# A6SS-3.net
KiCad netlist of a schematic drawn in EAGLE
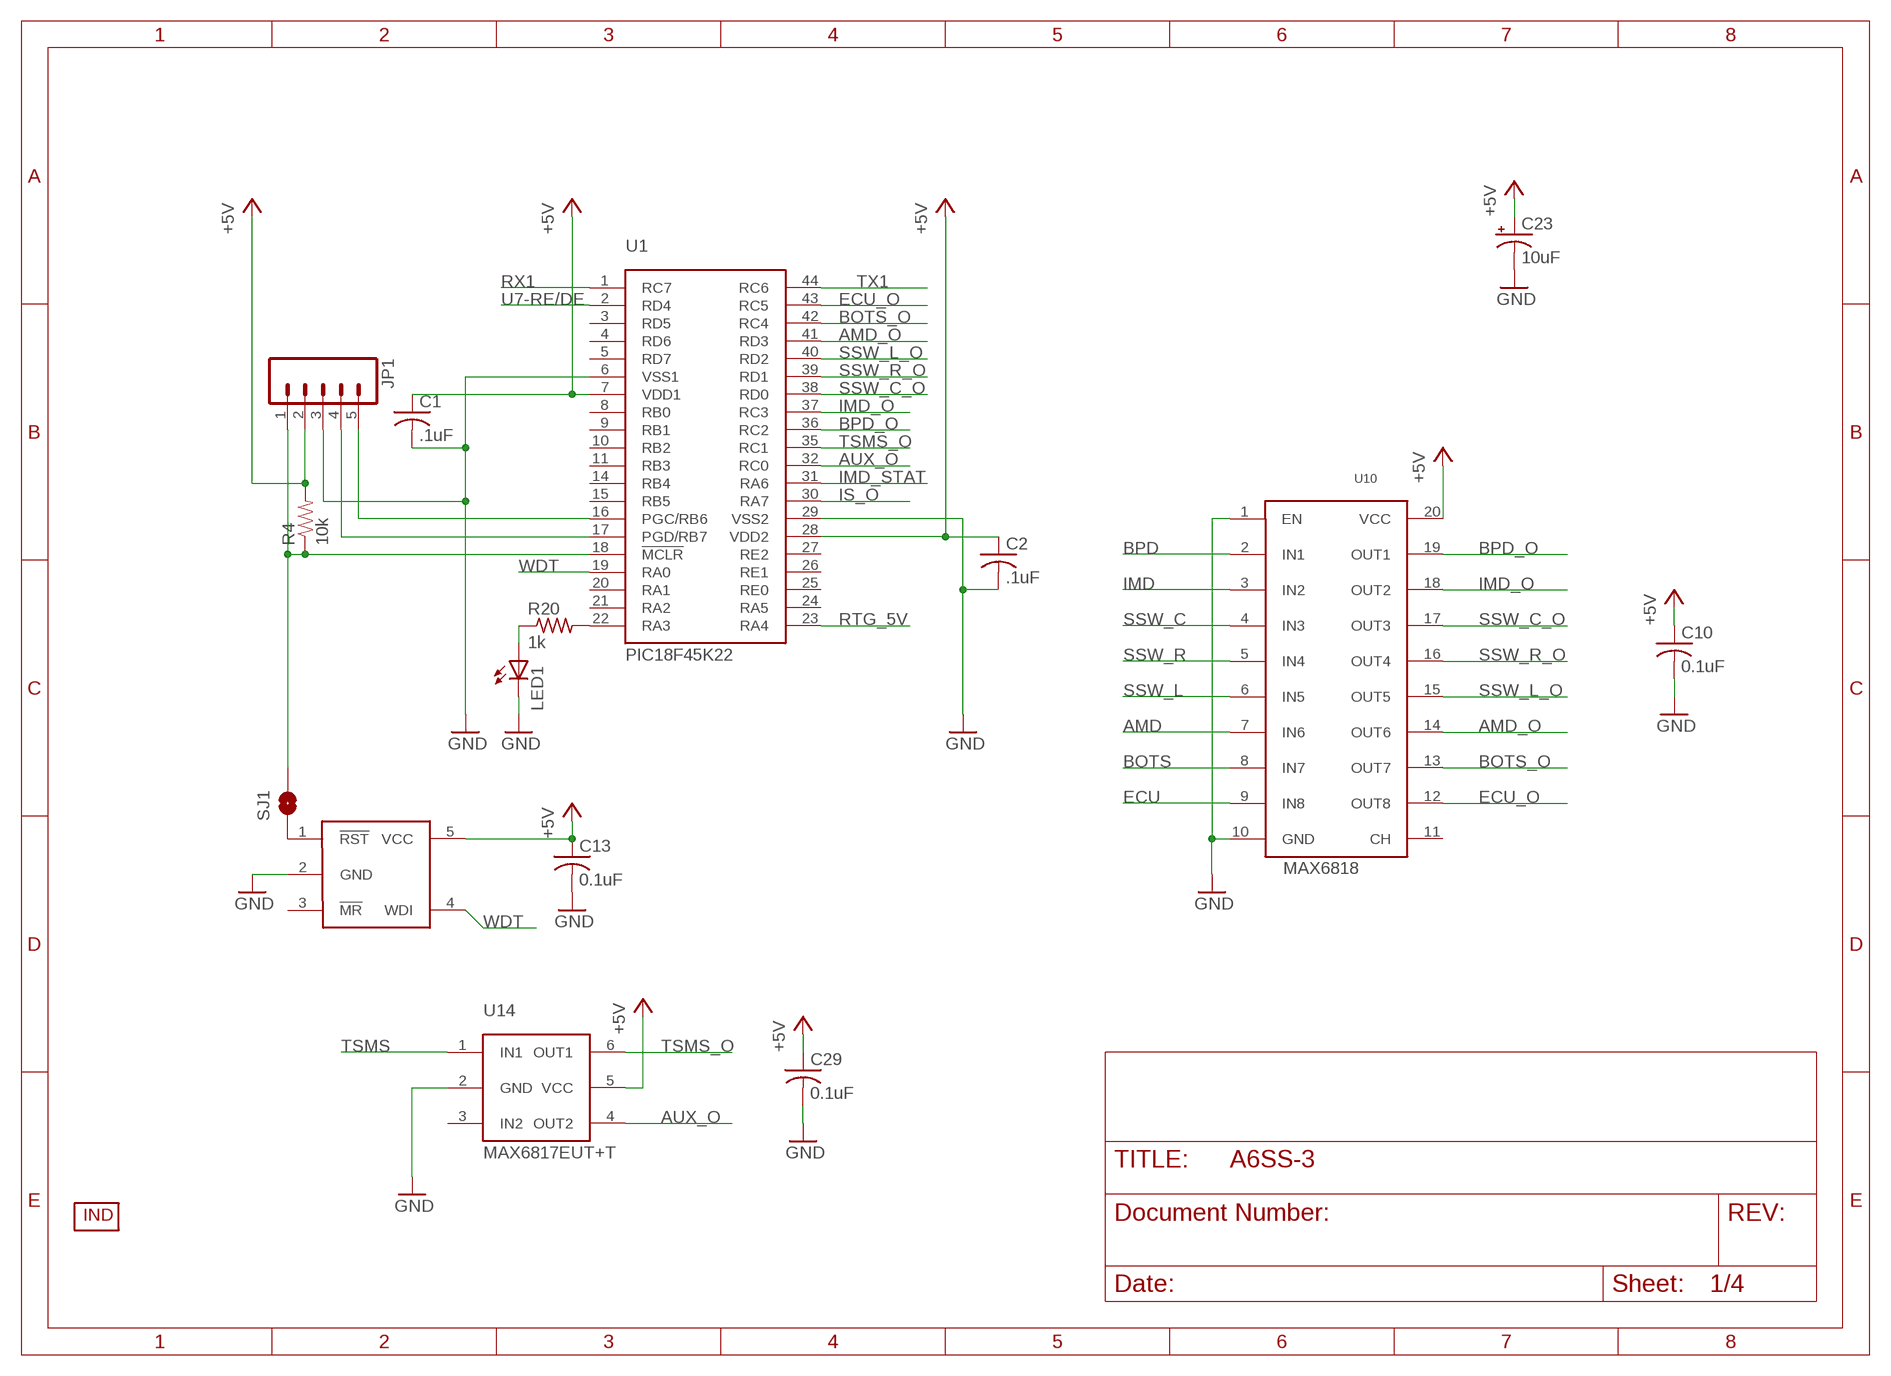
[diagram p0: schematic, sheet 1]
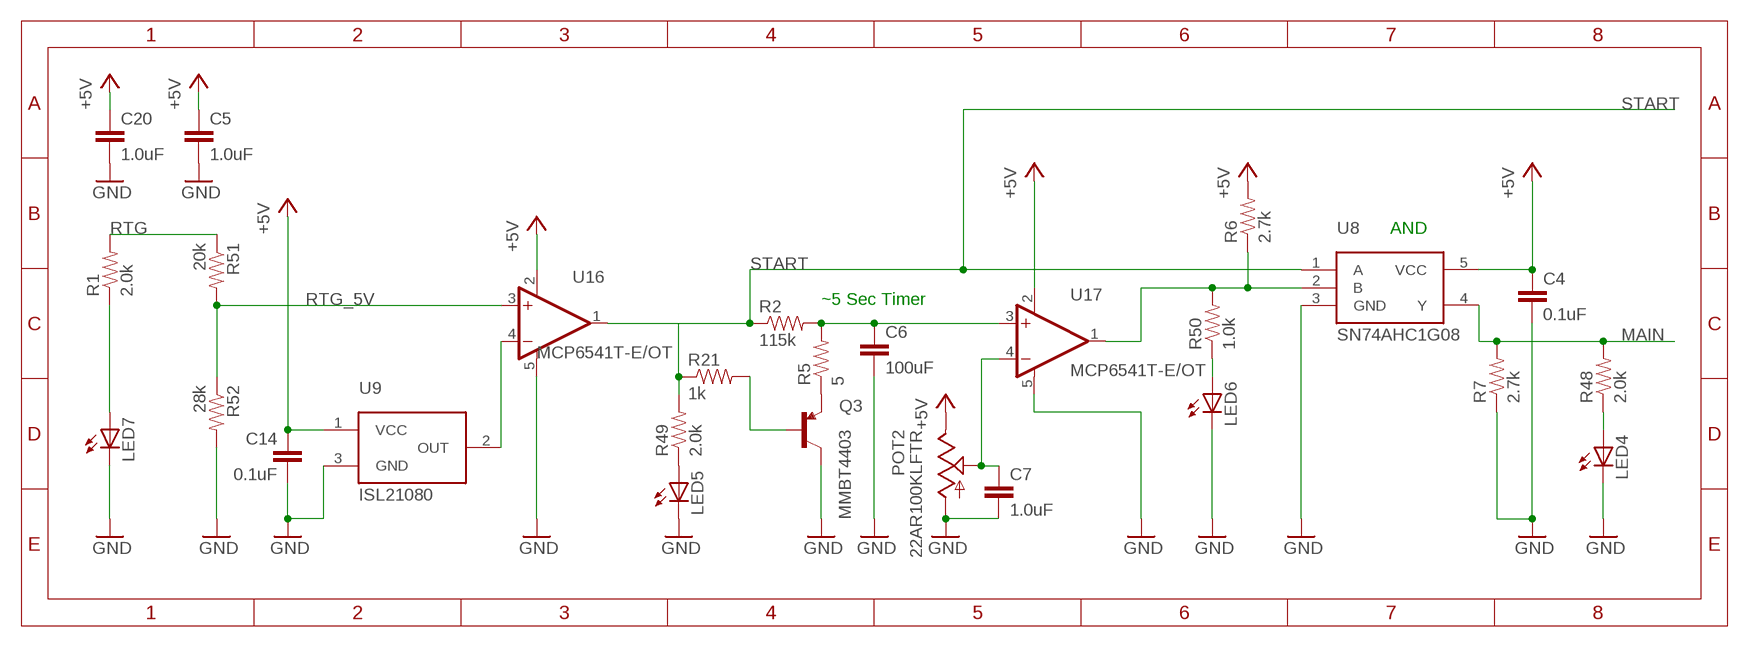
[diagram p1: schematic, sheet 2]
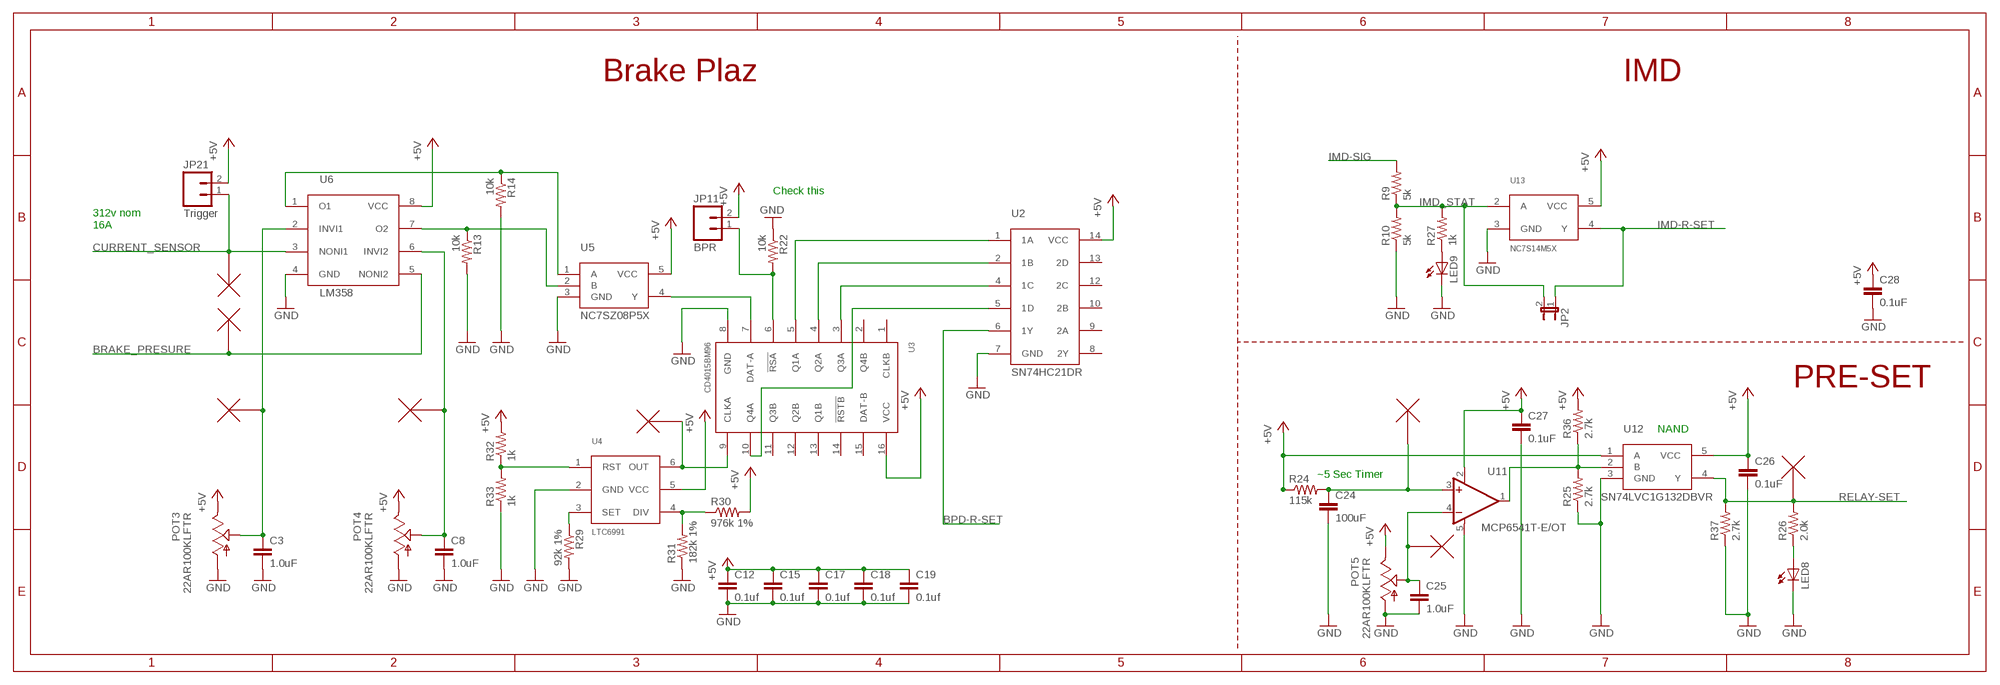
[diagram p2: schematic, sheet 3]
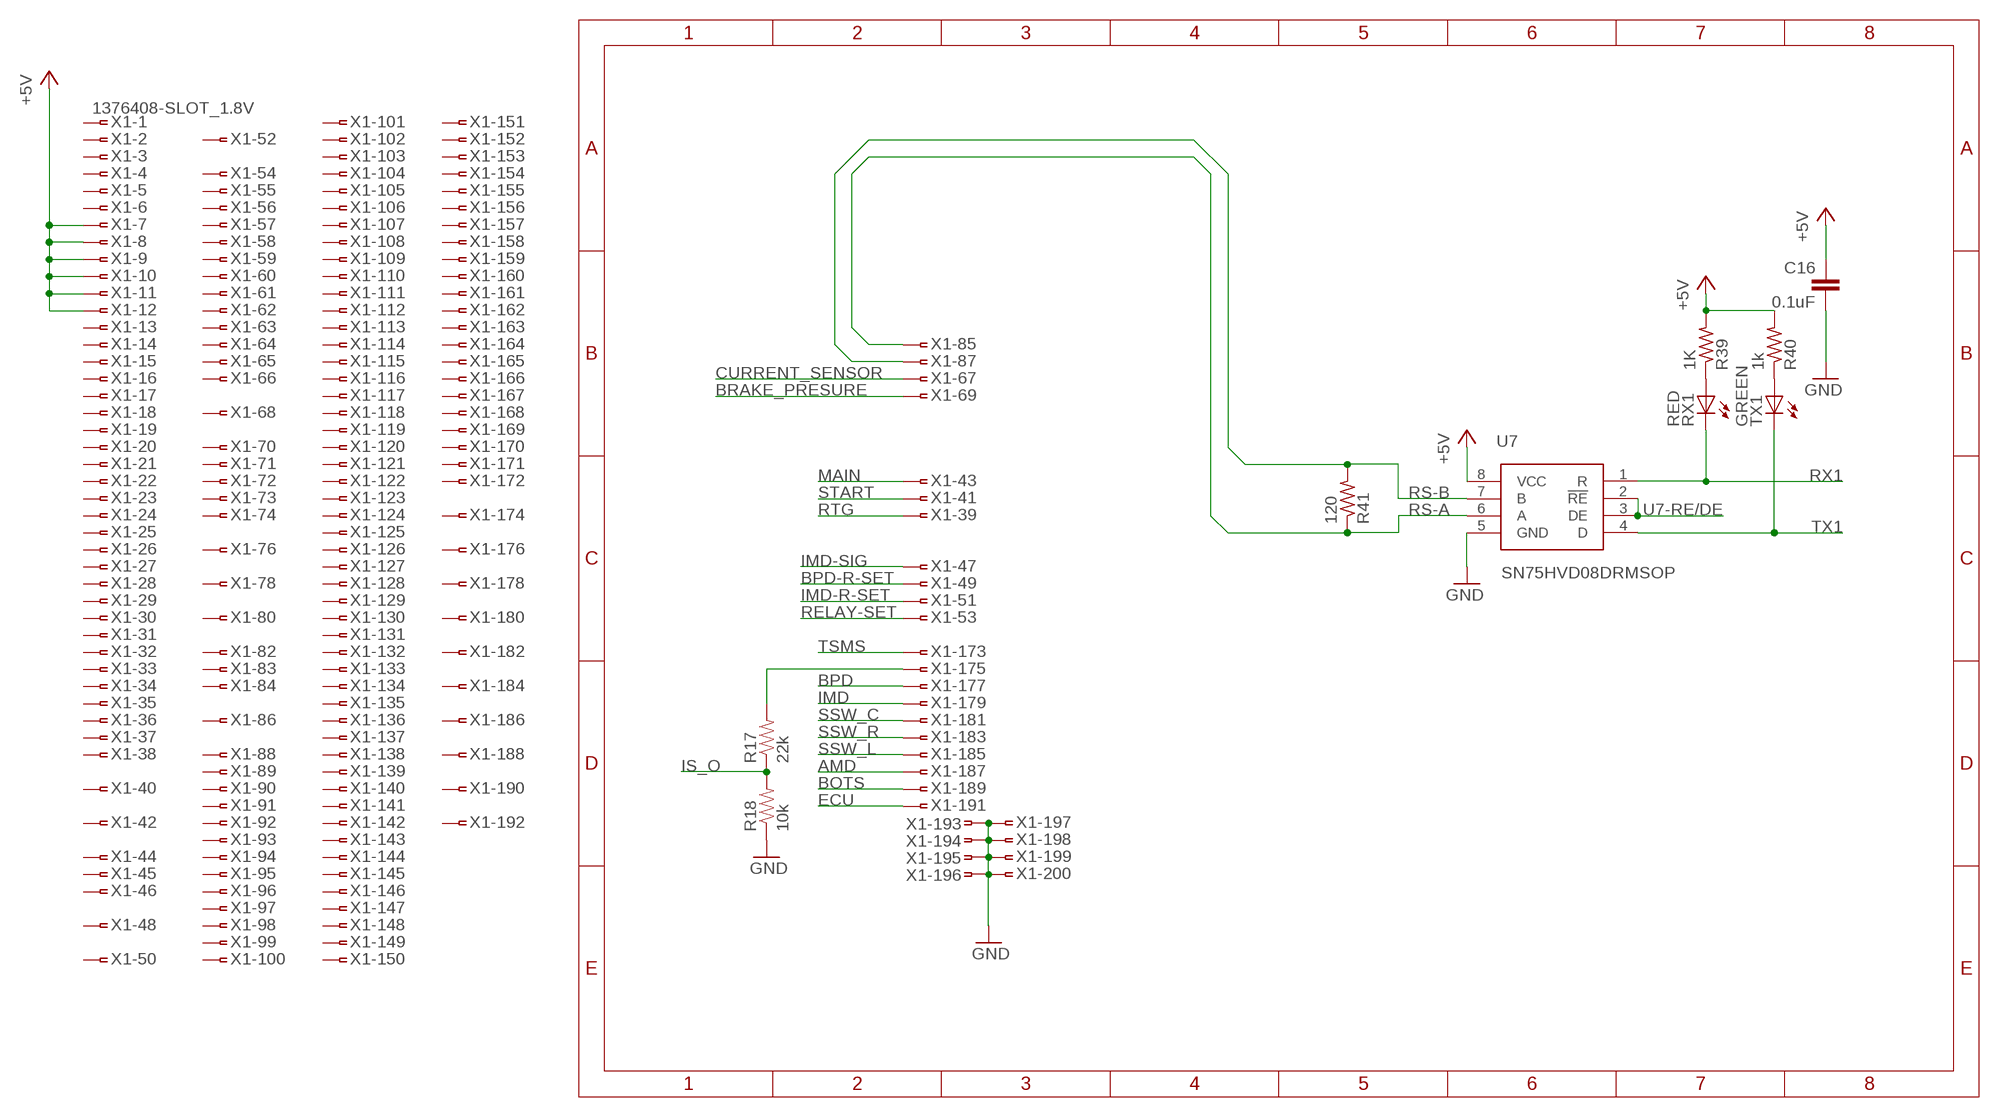
[diagram p3: schematic, sheet 4]

(export (version "E")
  (design (tool "Eeschema 10.0.6"))
  (components
    (comp (ref "C1")
      (value ".1uF")
      (footprint "eagle-import:C0603")
      (libsource (lib "eagle-import") (part "C-USC0603"))
    )
    (comp (ref "C2")
      (value ".1uF")
      (footprint "eagle-import:C0603")
      (libsource (lib "eagle-import") (part "C-USC0603"))
    )
    (comp (ref "C10")
      (value "0.1uF")
      (footprint "eagle-import:C0603")
      (libsource (lib "eagle-import") (part "C-USC0603"))
    )
    (comp (ref "C13")
      (value "0.1uF")
      (footprint "eagle-import:C0603")
      (libsource (lib "eagle-import") (part "C-USC0603"))
    )
    (comp (ref "C23")
      (value "10uF")
      (footprint "eagle-import:EIA3216")
      (libsource (lib "eagle-import") (part "10UF-TANT"))
    )
    (comp (ref "C29")
      (value "0.1uF")
      (footprint "eagle-import:C0603")
      (libsource (lib "eagle-import") (part "C-USC0603"))
    )
    (comp (ref "JP1")
      (value "M05LOCK_LONGPADS")
      (footprint "eagle-import:1X05_LOCK_LONGPADS")
      (libsource (lib "eagle-import") (part "M05LOCK_LONGPADS"))
    )
    (comp (ref "LED1")
      (value "LEDCHIPLED_0603")
      (footprint "eagle-import:CHIPLED_0603")
      (libsource (lib "eagle-import") (part "LEDCHIPLED_0603"))
    )
    (comp (ref "R4")
      (value "10k")
      (footprint "eagle-import:0603-RES")
      (libsource (lib "eagle-import") (part "RESISTOR0603-RES"))
    )
    (comp (ref "R20")
      (value "1k")
      (footprint "eagle-import:R0603")
      (libsource (lib "eagle-import") (part "R-US_R0603"))
    )
    (comp (ref "SJ1")
      (value "SOLDERJUMPERNO")
      (footprint "eagle-import:SJ_2S-NO")
      (libsource (lib "eagle-import") (part "SOLDERJUMPERNO"))
    )
    (comp (ref "U$1")
      (value "INDPK1")
      (footprint "eagle-import:PICKIT-PIN-1")
      (libsource (lib "eagle-import") (part "INDPK1"))
    )
    (comp (ref "U1")
      (value "PIC18F45K22")
      (footprint "eagle-import:TQFP-44")
      (libsource (lib "eagle-import") (part "PIC18F45K22"))
    )
    (comp (ref "U10")
      (value "MAX6818")
      (footprint "eagle-import:SSOP-20")
      (libsource (lib "eagle-import") (part "MAX6818"))
    )
    (comp (ref "U14")
      (value "MAX6817EUT+T")
      (footprint "eagle-import:SOT23-6")
      (libsource (lib "eagle-import") (part "MAX6817EUT+T"))
    )
    (comp (ref "U15")
      (value "MAX823")
      (footprint "eagle-import:SOT23-5L")
      (libsource (lib "eagle-import") (part "MAX823"))
    )
    (comp (ref "BPR")
      (value "TESTPOINT")
      (footprint "eagle-import:R0603")
      (libsource (lib "eagle-import") (part "TESTPOINT"))
    )
    (comp (ref "C3")
      (value "1.0uF")
      (footprint "eagle-import:0805")
      (libsource (lib "eagle-import") (part "1.0UF-25V-+80/-20(0805)"))
    )
    (comp (ref "C8")
      (value "1.0uF")
      (footprint "eagle-import:0805")
      (libsource (lib "eagle-import") (part "1.0UF-25V-+80/-20(0805)"))
    )
    (comp (ref "C12")
      (value "0.1uf")
      (footprint "eagle-import:0603-CAP")
      (libsource (lib "eagle-import") (part "SparkFun-Passives_CAP0603-CAP"))
    )
    (comp (ref "C15")
      (value "0.1uf")
      (footprint "eagle-import:0603-CAP")
      (libsource (lib "eagle-import") (part "SparkFun-Passives_CAP0603-CAP"))
    )
    (comp (ref "C17")
      (value "0.1uf")
      (footprint "eagle-import:0603-CAP")
      (libsource (lib "eagle-import") (part "SparkFun-Passives_CAP0603-CAP"))
    )
    (comp (ref "C18")
      (value "0.1uf")
      (footprint "eagle-import:0603-CAP")
      (libsource (lib "eagle-import") (part "SparkFun-Passives_CAP0603-CAP"))
    )
    (comp (ref "C19")
      (value "0.1uf")
      (footprint "eagle-import:0805")
      (libsource (lib "eagle-import") (part "SparkFun-Passives_CAP0805"))
    )
    (comp (ref "C24")
      (value "100uF")
      (footprint "eagle-import:1206")
      (libsource (lib "eagle-import") (part "CAP1206"))
    )
    (comp (ref "C25")
      (value "1.0uF")
      (footprint "eagle-import:0805")
      (libsource (lib "eagle-import") (part "SparkFun-Passives_CAP0805"))
    )
    (comp (ref "C26")
      (value "0.1uF")
      (footprint "eagle-import:0603-CAP")
      (libsource (lib "eagle-import") (part "SparkFun-Passives_CAP0603-CAP"))
    )
    (comp (ref "C27")
      (value "0.1uF")
      (footprint "eagle-import:0603-CAP")
      (libsource (lib "eagle-import") (part "SparkFun-Passives_CAP0603-CAP"))
    )
    (comp (ref "C28")
      (value "0.1uF")
      (footprint "eagle-import:0805")
      (libsource (lib "eagle-import") (part "SparkFun-Passives_CAP0805"))
    )
    (comp (ref "CLK")
      (value "TESTPOINT")
      (footprint "eagle-import:R0603")
      (libsource (lib "eagle-import") (part "TESTPOINT"))
    )
    (comp (ref "CS")
      (value "TESTPOINT")
      (footprint "eagle-import:R0603")
      (libsource (lib "eagle-import") (part "TESTPOINT"))
    )
    (comp (ref "CST")
      (value "TESTPOINT")
      (footprint "eagle-import:R0603")
      (libsource (lib "eagle-import") (part "TESTPOINT"))
    )
    (comp (ref "JP2")
      (value "JUMPER-2SMD-NO")
      (footprint "eagle-import:SJ_2S-NO")
      (libsource (lib "eagle-import") (part "JUMPER-2SMD-NO"))
    )
    (comp (ref "JP11")
      (value "BPR")
      (footprint "eagle-import:MOLEX-1X2_LOCK")
      (libsource (lib "eagle-import") (part "M02POLAR_LOCK"))
    )
    (comp (ref "JP21")
      (value "Trigger")
      (footprint "eagle-import:MOLEX-1X2_LOCK")
      (libsource (lib "eagle-import") (part "M02POLAR_LOCK"))
    )
    (comp (ref "LED8")
      (value "LEDCHIPLED_0603")
      (footprint "eagle-import:CHIPLED_0603")
      (libsource (lib "eagle-import") (part "LEDCHIPLED_0603"))
    )
    (comp (ref "LED9")
      (value "LEDCHIPLED_0603")
      (footprint "eagle-import:CHIPLED_0603")
      (libsource (lib "eagle-import") (part "LEDCHIPLED_0603"))
    )
    (comp (ref "PCG")
      (value "TESTPOINT")
      (footprint "eagle-import:R0603")
      (libsource (lib "eagle-import") (part "TESTPOINT"))
    )
    (comp (ref "POT3")
      (value "22AR100KLFTR")
      (footprint "eagle-import:22AR100KLFTR")
      (libsource (lib "eagle-import") (part "22AR100KLFTR"))
    )
    (comp (ref "POT4")
      (value "22AR100KLFTR")
      (footprint "eagle-import:22AR100KLFTR")
      (libsource (lib "eagle-import") (part "22AR100KLFTR"))
    )
    (comp (ref "POT5")
      (value "22AR100KLFTR")
      (footprint "eagle-import:22AR100KLFTR")
      (libsource (lib "eagle-import") (part "22AR100KLFTR"))
    )
    (comp (ref "R9")
      (value "5k")
      (footprint "eagle-import:0603-RES")
      (libsource (lib "eagle-import") (part "RESISTOR0603-RES"))
    )
    (comp (ref "R10")
      (value "5k")
      (footprint "eagle-import:0603-RES")
      (libsource (lib "eagle-import") (part "RESISTOR0603-RES"))
    )
    (comp (ref "R13")
      (value "10k")
      (footprint "eagle-import:0603-RES")
      (libsource (lib "eagle-import") (part "SparkFun-Resistors_RESISTOR0603-RES"))
    )
    (comp (ref "R14")
      (value "10k")
      (footprint "eagle-import:0603-RES")
      (libsource (lib "eagle-import") (part "SparkFun-Resistors_RESISTOR0603-RES"))
    )
    (comp (ref "R22")
      (value "10k")
      (footprint "eagle-import:0603-RES")
      (libsource (lib "eagle-import") (part "SparkFun-Resistors_RESISTOR0603-RES"))
    )
    (comp (ref "R24")
      (value "115k")
      (footprint "eagle-import:1206")
      (libsource (lib "eagle-import") (part "SparkFun-Resistors_RESISTOR1206"))
    )
    (comp (ref "R25")
      (value "2.7k")
      (footprint "eagle-import:0603-RES")
      (libsource (lib "eagle-import") (part "RESISTOR0603-RES"))
    )
    (comp (ref "R26")
      (value "2.0k")
      (footprint "eagle-import:0603-RES")
      (libsource (lib "eagle-import") (part "RESISTOR0603-RES"))
    )
    (comp (ref "R27")
      (value "1k")
      (footprint "eagle-import:0603-RES")
      (libsource (lib "eagle-import") (part "RESISTOR0603-RES"))
    )
    (comp (ref "R29")
      (value "92k 1%")
      (footprint "eagle-import:0603-RES")
      (libsource (lib "eagle-import") (part "SparkFun-Resistors_RESISTOR0603-RES"))
    )
    (comp (ref "R30")
      (value "976k 1%")
      (footprint "eagle-import:0603-RES")
      (libsource (lib "eagle-import") (part "SparkFun-Resistors_RESISTOR0603-RES"))
    )
    (comp (ref "R31")
      (value "182k 1%")
      (footprint "eagle-import:0603-RES")
      (libsource (lib "eagle-import") (part "SparkFun-Resistors_RESISTOR0603-RES"))
    )
    (comp (ref "R32")
      (value "1k")
      (footprint "eagle-import:0603-RES")
      (libsource (lib "eagle-import") (part "SparkFun-Resistors_RESISTOR0603-RES"))
    )
    (comp (ref "R33")
      (value "1k")
      (footprint "eagle-import:0603-RES")
      (libsource (lib "eagle-import") (part "SparkFun-Resistors_RESISTOR0603-RES"))
    )
    (comp (ref "R36")
      (value "2.7k")
      (footprint "eagle-import:0603-RES")
      (libsource (lib "eagle-import") (part "RESISTOR0603-RES"))
    )
    (comp (ref "R37")
      (value "2.7k")
      (footprint "eagle-import:0603-RES")
      (libsource (lib "eagle-import") (part "RESISTOR0603-RES"))
    )
    (comp (ref "RST")
      (value "TESTPOINT")
      (footprint "eagle-import:R0603")
      (libsource (lib "eagle-import") (part "TESTPOINT"))
    )
    (comp (ref "U$2")
      (value "TESTPOINT")
      (footprint "eagle-import:R0603")
      (libsource (lib "eagle-import") (part "TESTPOINT"))
    )
    (comp (ref "U$3")
      (value "TESTPOINT")
      (footprint "eagle-import:R0603")
      (libsource (lib "eagle-import") (part "TESTPOINT"))
    )
    (comp (ref "U2")
      (value "SN74HC21DR")
      (footprint "eagle-import:SO14")
      (libsource (lib "eagle-import") (part "SN74HC20DR"))
    )
    (comp (ref "U3")
      (value "CD4015BM96")
      (footprint "eagle-import:SO-16")
      (libsource (lib "eagle-import") (part "CD4015BM96"))
    )
    (comp (ref "U4")
      (value "LTC6991")
      (footprint "eagle-import:TSOT-23-6")
      (libsource (lib "eagle-import") (part "LTC6991"))
    )
    (comp (ref "U5")
      (value "NC7SZ08P5X")
      (footprint "eagle-import:SOT23-5")
      (libsource (lib "eagle-import") (part "NC7SZ08P5X"))
    )
    (comp (ref "U6")
      (value "LM358")
      (footprint "eagle-import:TSSOP-8")
      (libsource (lib "eagle-import") (part "LM358"))
    )
    (comp (ref "U11")
      (value "MCP6541T-E/OT")
      (footprint "eagle-import:SOT23-5")
      (libsource (lib "eagle-import") (part "OPA344"))
    )
    (comp (ref "U12")
      (value "SN74LVC1G132DBVR")
      (footprint "eagle-import:SOT23-5")
      (libsource (lib "eagle-import") (part "NC7SZ08P5X"))
    )
    (comp (ref "U13")
      (value "NC7S14M5X")
      (footprint "eagle-import:SOT23-5")
      (libsource (lib "eagle-import") (part "NC7S14M5X"))
    )
    (comp (ref "C16")
      (value "0.1uF")
      (footprint "eagle-import:0603-CAP")
      (libsource (lib "eagle-import") (part "SparkFun-Passives_CAP0603-CAP"))
    )
    (comp (ref "R17")
      (value "22k")
      (footprint "eagle-import:0805")
      (libsource (lib "eagle-import") (part "RESISTOR0805-RES"))
    )
    (comp (ref "R18")
      (value "10k")
      (footprint "eagle-import:0805")
      (libsource (lib "eagle-import") (part "RESISTOR0805-RES"))
    )
    (comp (ref "R39")
      (value "1K")
      (footprint "eagle-import:R0603")
      (libsource (lib "eagle-import") (part "R-US_R0603"))
    )
    (comp (ref "R40")
      (value "1k")
      (footprint "eagle-import:R0603")
      (libsource (lib "eagle-import") (part "R-US_R0603"))
    )
    (comp (ref "R41")
      (value "120")
      (footprint "eagle-import:R0603")
      (libsource (lib "eagle-import") (part "R-US_R0603"))
    )
    (comp (ref "RX1")
      (value "RED")
      (footprint "eagle-import:CHIPLED_0603")
      (libsource (lib "eagle-import") (part "LEDCHIPLED_0603"))
    )
    (comp (ref "TX1")
      (value "GREEN")
      (footprint "eagle-import:CHIPLED_0603")
      (libsource (lib "eagle-import") (part "LEDCHIPLED_0603"))
    )
    (comp (ref "U7")
      (value "SN75HVD08DRMSOP")
      (footprint "eagle-import:MSOP-8")
      (libsource (lib "eagle-import") (part "SN75HVD08DRMSOP"))
    )
    (comp (ref "X1")
      (value "1376408-SLOT_1.8V")
      (footprint "eagle-import:SLOT-1376408-1_1.8V")
      (libsource (lib "eagle-import") (part "1376408-SLOT_1.8V"))
    )
    (comp (ref "C4")
      (value "0.1uF")
      (footprint "eagle-import:0603-CAP")
      (libsource (lib "eagle-import") (part "SparkFun-Passives_CAP0603-CAP"))
    )
    (comp (ref "C5")
      (value "1.0uF")
      (footprint "eagle-import:0603-CAP")
      (libsource (lib "eagle-import") (part "SparkFun-Passives_CAP0603-CAP"))
    )
    (comp (ref "C6")
      (value "100uF")
      (footprint "eagle-import:1206")
      (libsource (lib "eagle-import") (part "CAP1206"))
    )
    (comp (ref "C7")
      (value "1.0uF")
      (footprint "eagle-import:0805")
      (libsource (lib "eagle-import") (part "SparkFun-Passives_CAP0805"))
    )
    (comp (ref "C14")
      (value "0.1uF")
      (footprint "eagle-import:0603-CAP")
      (libsource (lib "eagle-import") (part "SparkFun-Passives_CAP0603-CAP"))
    )
    (comp (ref "C20")
      (value "1.0uF")
      (footprint "eagle-import:0805")
      (libsource (lib "eagle-import") (part "SparkFun-Passives_CAP0805"))
    )
    (comp (ref "LED4")
      (value "LEDCHIPLED_0603")
      (footprint "eagle-import:CHIPLED_0603")
      (libsource (lib "eagle-import") (part "LEDCHIPLED_0603"))
    )
    (comp (ref "LED5")
      (value "LEDCHIPLED_0603")
      (footprint "eagle-import:CHIPLED_0603")
      (libsource (lib "eagle-import") (part "LEDCHIPLED_0603"))
    )
    (comp (ref "LED6")
      (value "LEDCHIPLED_0603")
      (footprint "eagle-import:CHIPLED_0603")
      (libsource (lib "eagle-import") (part "LEDCHIPLED_0603"))
    )
    (comp (ref "LED7")
      (value "LEDCHIPLED_0603")
      (footprint "eagle-import:CHIPLED_0603")
      (libsource (lib "eagle-import") (part "LEDCHIPLED_0603"))
    )
    (comp (ref "POT2")
      (value "22AR100KLFTR")
      (footprint "eagle-import:22AR100KLFTR")
      (libsource (lib "eagle-import") (part "22AR100KLFTR"))
    )
    (comp (ref "Q3")
      (value "MMBT4403")
      (footprint "eagle-import:SOT23")
      (libsource (lib "eagle-import") (part "TRANSISTOR_PNPMMBT4403"))
    )
    (comp (ref "R1")
      (value "2.0k")
      (footprint "eagle-import:0603-RES")
      (libsource (lib "eagle-import") (part "RESISTOR0603-RES"))
    )
    (comp (ref "R2")
      (value "115k")
      (footprint "eagle-import:1206")
      (libsource (lib "eagle-import") (part "SparkFun-Resistors_RESISTOR1206"))
    )
    (comp (ref "R5")
      (value "5")
      (footprint "eagle-import:0603-RES")
      (libsource (lib "eagle-import") (part "RESISTOR0603-RES"))
    )
    (comp (ref "R6")
      (value "2.7k")
      (footprint "eagle-import:0603-RES")
      (libsource (lib "eagle-import") (part "RESISTOR0603-RES"))
    )
    (comp (ref "R7")
      (value "2.7k")
      (footprint "eagle-import:0603-RES")
      (libsource (lib "eagle-import") (part "RESISTOR0603-RES"))
    )
    (comp (ref "R21")
      (value "1k")
      (footprint "eagle-import:0603-RES")
      (libsource (lib "eagle-import") (part "RESISTOR0603-RES"))
    )
    (comp (ref "R48")
      (value "2.0k")
      (footprint "eagle-import:0603-RES")
      (libsource (lib "eagle-import") (part "RESISTOR0603-RES"))
    )
    (comp (ref "R49")
      (value "2.0k")
      (footprint "eagle-import:0603-RES")
      (libsource (lib "eagle-import") (part "RESISTOR0603-RES"))
    )
    (comp (ref "R50")
      (value "1.0k")
      (footprint "eagle-import:0603-RES")
      (libsource (lib "eagle-import") (part "RESISTOR0603-RES"))
    )
    (comp (ref "R51")
      (value "20k")
      (footprint "eagle-import:0603-RES")
      (libsource (lib "eagle-import") (part "SparkFun-Resistors_RESISTOR0603-RES"))
    )
    (comp (ref "R52")
      (value "28k")
      (footprint "eagle-import:0603-RES")
      (libsource (lib "eagle-import") (part "SparkFun-Resistors_RESISTOR0603-RES"))
    )
    (comp (ref "U8")
      (value "SN74AHC1G08")
      (footprint "eagle-import:SOT23-5")
      (libsource (lib "eagle-import") (part "NC7SZ08P5X"))
    )
    (comp (ref "U9")
      (value "ISL21080")
      (footprint "eagle-import:SOT-23")
      (libsource (lib "eagle-import") (part "ISL21080"))
    )
    (comp (ref "U16")
      (value "MCP6541T-E/OT")
      (footprint "eagle-import:SOT23-5")
      (libsource (lib "eagle-import") (part "OPA344"))
    )
    (comp (ref "U17")
      (value "MCP6541T-E/OT")
      (footprint "eagle-import:SOT23-5")
      (libsource (lib "eagle-import") (part "OPA344"))
    )
  )
  (nets
    (net (code "1") (name "+5V") (class "Default")
      (node (ref "C1") (pin "1") (pinfunction "1_1") (pintype "passive"))
      (node (ref "C10") (pin "1") (pinfunction "1_1") (pintype "passive"))
      (node (ref "C12") (pin "1") (pinfunction "1_1") (pintype "passive"))
      (node (ref "C13") (pin "1") (pinfunction "1_1") (pintype "passive"))
      (node (ref "C14") (pin "1") (pinfunction "1_1") (pintype "passive"))
      (node (ref "C15") (pin "1") (pinfunction "1_1") (pintype "passive"))
      (node (ref "C16") (pin "1") (pinfunction "1_1") (pintype "passive"))
      (node (ref "C17") (pin "1") (pinfunction "1_1") (pintype "passive"))
      (node (ref "C18") (pin "1") (pinfunction "1_1") (pintype "passive"))
      (node (ref "C19") (pin "1") (pinfunction "1_1") (pintype "passive"))
      (node (ref "C2") (pin "1") (pinfunction "1_1") (pintype "passive"))
      (node (ref "C20") (pin "1") (pinfunction "1_1") (pintype "passive"))
      (node (ref "C23") (pin "A") (pinfunction "+_A") (pintype "passive"))
      (node (ref "C26") (pin "1") (pinfunction "1_1") (pintype "passive"))
      (node (ref "C27") (pin "1") (pinfunction "1_1") (pintype "passive"))
      (node (ref "C28") (pin "1") (pinfunction "1_1") (pintype "passive"))
      (node (ref "C29") (pin "1") (pinfunction "1_1") (pintype "passive"))
      (node (ref "C4") (pin "1") (pinfunction "1_1") (pintype "passive"))
      (node (ref "C5") (pin "1") (pinfunction "1_1") (pintype "passive"))
      (node (ref "JP1") (pin "2") (pinfunction "2_2") (pintype "passive"))
      (node (ref "JP11") (pin "2") (pinfunction "2_2") (pintype "passive"))
      (node (ref "JP21") (pin "2") (pinfunction "2_2") (pintype "passive"))
      (node (ref "POT2") (pin "1") (pinfunction "CCW_1") (pintype "passive"))
      (node (ref "POT3") (pin "1") (pinfunction "CCW_1") (pintype "passive"))
      (node (ref "POT4") (pin "1") (pinfunction "CCW_1") (pintype "passive"))
      (node (ref "POT5") (pin "1") (pinfunction "CCW_1") (pintype "passive"))
      (node (ref "R24") (pin "1") (pinfunction "1_1") (pintype "passive"))
      (node (ref "R30") (pin "2") (pinfunction "2_2") (pintype "passive"))
      (node (ref "R32") (pin "2") (pinfunction "2_2") (pintype "passive"))
      (node (ref "R36") (pin "2") (pinfunction "2_2") (pintype "passive"))
      (node (ref "R39") (pin "2") (pinfunction "2_2") (pintype "passive"))
      (node (ref "R4") (pin "2") (pinfunction "2_2") (pintype "passive"))
      (node (ref "R40") (pin "2") (pinfunction "2_2") (pintype "passive"))
      (node (ref "R6") (pin "2") (pinfunction "2_2") (pintype "passive"))
      (node (ref "U1") (pin "28") (pinfunction "VDD2_28") (pintype "bidirectional"))
      (node (ref "U1") (pin "7") (pinfunction "VDD1_7") (pintype "bidirectional"))
      (node (ref "U10") (pin "20") (pinfunction "VCC_20") (pintype "bidirectional"))
      (node (ref "U11") (pin "2") (pinfunction "V-_2") (pintype "power_in"))
      (node (ref "U12") (pin "1") (pinfunction "A_1") (pintype "bidirectional"))
      (node (ref "U12") (pin "5") (pinfunction "VCC_5") (pintype "bidirectional"))
      (node (ref "U13") (pin "5") (pinfunction "VCC_5") (pintype "bidirectional"))
      (node (ref "U14") (pin "5") (pinfunction "VCC_5") (pintype "bidirectional"))
      (node (ref "U15") (pin "5") (pinfunction "VCC_5") (pintype "bidirectional"))
      (node (ref "U16") (pin "2") (pinfunction "V-_2") (pintype "power_in"))
      (node (ref "U17") (pin "2") (pinfunction "V-_2") (pintype "power_in"))
      (node (ref "U2") (pin "14") (pinfunction "VCC_14") (pintype "bidirectional"))
      (node (ref "U3") (pin "16") (pinfunction "VCC_16") (pintype "bidirectional"))
      (node (ref "U4") (pin "5") (pinfunction "VCC_5") (pintype "bidirectional"))
      (node (ref "U5") (pin "5") (pinfunction "VCC_5") (pintype "bidirectional"))
      (node (ref "U6") (pin "8") (pinfunction "VCC_8") (pintype "bidirectional"))
      (node (ref "U7") (pin "8") (pinfunction "VCC_8") (pintype "bidirectional"))
      (node (ref "U8") (pin "5") (pinfunction "VCC_5") (pintype "bidirectional"))
      (node (ref "U9") (pin "1") (pinfunction "VCC_1") (pintype "bidirectional"))
      (node (ref "X1") (pin "10") (pinfunction "1_10") (pintype "passive"))
      (node (ref "X1") (pin "11") (pinfunction "1_11") (pintype "passive"))
      (node (ref "X1") (pin "12") (pinfunction "1_12") (pintype "passive"))
      (node (ref "X1") (pin "7") (pinfunction "1_7") (pintype "passive"))
      (node (ref "X1") (pin "8") (pinfunction "1_8") (pintype "passive"))
      (node (ref "X1") (pin "9") (pinfunction "1_9") (pintype "passive"))
    )
    (net (code "2") (name "AMD") (class "Default")
      (node (ref "U10") (pin "7") (pinfunction "IN6_7") (pintype "bidirectional"))
      (node (ref "X1") (pin "187") (pinfunction "1_187") (pintype "passive"))
    )
    (net (code "3") (name "AMD_O") (class "Default")
      (node (ref "U1") (pin "41") (pinfunction "RD3_41") (pintype "bidirectional"))
      (node (ref "U10") (pin "14") (pinfunction "OUT6_14") (pintype "bidirectional"))
    )
    (net (code "4") (name "AUX_O") (class "Default")
      (node (ref "U1") (pin "32") (pinfunction "RC0_32") (pintype "bidirectional"))
      (node (ref "U14") (pin "4") (pinfunction "OUT2_4") (pintype "bidirectional"))
    )
    (net (code "5") (name "BOTS") (class "Default")
      (node (ref "U10") (pin "8") (pinfunction "IN7_8") (pintype "bidirectional"))
      (node (ref "X1") (pin "189") (pinfunction "1_189") (pintype "passive"))
    )
    (net (code "6") (name "BOTS_O") (class "Default")
      (node (ref "U1") (pin "42") (pinfunction "RC4_42") (pintype "bidirectional"))
      (node (ref "U10") (pin "13") (pinfunction "OUT7_13") (pintype "bidirectional"))
    )
    (net (code "7") (name "BPD") (class "Default")
      (node (ref "U10") (pin "2") (pinfunction "IN1_2") (pintype "bidirectional"))
      (node (ref "X1") (pin "177") (pinfunction "1_177") (pintype "passive"))
    )
    (net (code "8") (name "BPD-R-SET") (class "Default")
      (node (ref "U2") (pin "6") (pinfunction "1Y_6") (pintype "bidirectional"))
      (node (ref "X1") (pin "49") (pinfunction "1_49") (pintype "passive"))
    )
    (net (code "9") (name "BPD_O") (class "Default")
      (node (ref "U1") (pin "36") (pinfunction "RC2_36") (pintype "bidirectional"))
      (node (ref "U10") (pin "19") (pinfunction "OUT1_19") (pintype "bidirectional"))
    )
    (net (code "10") (name "BRAKE_PRESURE") (class "Default")
      (node (ref "BPR") (pin "1") (pinfunction "P$1_1") (pintype "bidirectional"))
      (node (ref "BPR") (pin "2") (pinfunction "P$1_2") (pintype "bidirectional"))
      (node (ref "U6") (pin "5") (pinfunction "NONI2_5") (pintype "bidirectional"))
      (node (ref "X1") (pin "69") (pinfunction "1_69") (pintype "passive"))
    )
    (net (code "11") (name "CURRENT_SENSOR") (class "Default")
      (node (ref "CS") (pin "1") (pinfunction "P$1_1") (pintype "bidirectional"))
      (node (ref "CS") (pin "2") (pinfunction "P$1_2") (pintype "bidirectional"))
      (node (ref "JP21") (pin "1") (pinfunction "1_1") (pintype "passive"))
      (node (ref "U6") (pin "3") (pinfunction "NONI1_3") (pintype "bidirectional"))
      (node (ref "X1") (pin "67") (pinfunction "1_67") (pintype "passive"))
    )
    (net (code "12") (name "ECU") (class "Default")
      (node (ref "U10") (pin "9") (pinfunction "IN8_9") (pintype "bidirectional"))
      (node (ref "X1") (pin "191") (pinfunction "1_191") (pintype "passive"))
    )
    (net (code "13") (name "ECU_O") (class "Default")
      (node (ref "U1") (pin "43") (pinfunction "RC5_43") (pintype "bidirectional"))
      (node (ref "U10") (pin "12") (pinfunction "OUT8_12") (pintype "bidirectional"))
    )
    (net (code "14") (name "GND") (class "Default")
      (node (ref "C1") (pin "2") (pinfunction "2_2") (pintype "passive"))
      (node (ref "C10") (pin "2") (pinfunction "2_2") (pintype "passive"))
      (node (ref "C12") (pin "2") (pinfunction "2_2") (pintype "passive"))
      (node (ref "C13") (pin "2") (pinfunction "2_2") (pintype "passive"))
      (node (ref "C14") (pin "2") (pinfunction "2_2") (pintype "passive"))
      (node (ref "C15") (pin "2") (pinfunction "2_2") (pintype "passive"))
      (node (ref "C16") (pin "2") (pinfunction "2_2") (pintype "passive"))
      (node (ref "C17") (pin "2") (pinfunction "2_2") (pintype "passive"))
      (node (ref "C18") (pin "2") (pinfunction "2_2") (pintype "passive"))
      (node (ref "C19") (pin "2") (pinfunction "2_2") (pintype "passive"))
      (node (ref "C2") (pin "2") (pinfunction "2_2") (pintype "passive"))
      (node (ref "C20") (pin "2") (pinfunction "2_2") (pintype "passive"))
      (node (ref "C23") (pin "C") (pinfunction "-_C") (pintype "passive"))
      (node (ref "C24") (pin "2") (pinfunction "2_2") (pintype "passive"))
      (node (ref "C25") (pin "2") (pinfunction "2_2") (pintype "passive"))
      (node (ref "C26") (pin "2") (pinfunction "2_2") (pintype "passive"))
      (node (ref "C27") (pin "2") (pinfunction "2_2") (pintype "passive"))
      (node (ref "C28") (pin "2") (pinfunction "2_2") (pintype "passive"))
      (node (ref "C29") (pin "2") (pinfunction "2_2") (pintype "passive"))
      (node (ref "C3") (pin "2") (pinfunction "2_2") (pintype "passive"))
      (node (ref "C4") (pin "2") (pinfunction "2_2") (pintype "passive"))
      (node (ref "C5") (pin "2") (pinfunction "2_2") (pintype "passive"))
      (node (ref "C6") (pin "2") (pinfunction "2_2") (pintype "passive"))
      (node (ref "C7") (pin "2") (pinfunction "2_2") (pintype "passive"))
      (node (ref "C8") (pin "2") (pinfunction "2_2") (pintype "passive"))
      (node (ref "JP1") (pin "3") (pinfunction "3_3") (pintype "passive"))
      (node (ref "LED1") (pin "C") (pinfunction "C_C") (pintype "passive"))
      (node (ref "LED4") (pin "C") (pinfunction "C_C") (pintype "passive"))
      (node (ref "LED5") (pin "C") (pinfunction "C_C") (pintype "passive"))
      (node (ref "LED6") (pin "C") (pinfunction "C_C") (pintype "passive"))
      (node (ref "LED7") (pin "C") (pinfunction "C_C") (pintype "passive"))
      (node (ref "LED8") (pin "C") (pinfunction "C_C") (pintype "passive"))
      (node (ref "LED9") (pin "C") (pinfunction "C_C") (pintype "passive"))
      (node (ref "POT2") (pin "3") (pinfunction "CW_3") (pintype "passive"))
      (node (ref "POT3") (pin "3") (pinfunction "CW_3") (pintype "passive"))
      (node (ref "POT4") (pin "3") (pinfunction "CW_3") (pintype "passive"))
      (node (ref "POT5") (pin "3") (pinfunction "CW_3") (pintype "passive"))
      (node (ref "Q3") (pin "3") (pinfunction "C_3") (pintype "passive"))
      (node (ref "R10") (pin "1") (pinfunction "1_1") (pintype "passive"))
      (node (ref "R13") (pin "2") (pinfunction "2_2") (pintype "passive"))
      (node (ref "R14") (pin "2") (pinfunction "2_2") (pintype "passive"))
      (node (ref "R18") (pin "1") (pinfunction "1_1") (pintype "passive"))
      (node (ref "R22") (pin "1") (pinfunction "1_1") (pintype "passive"))
      (node (ref "R25") (pin "1") (pinfunction "1_1") (pintype "passive"))
      (node (ref "R29") (pin "2") (pinfunction "2_2") (pintype "passive"))
      (node (ref "R31") (pin "1") (pinfunction "1_1") (pintype "passive"))
      (node (ref "R33") (pin "1") (pinfunction "1_1") (pintype "passive"))
      (node (ref "R37") (pin "1") (pinfunction "1_1") (pintype "passive"))
      (node (ref "R52") (pin "2") (pinfunction "2_2") (pintype "passive"))
      (node (ref "R7") (pin "1") (pinfunction "1_1") (pintype "passive"))
      (node (ref "U1") (pin "29") (pinfunction "VSS2_29") (pintype "bidirectional"))
      (node (ref "U1") (pin "6") (pinfunction "VSS1_6") (pintype "bidirectional"))
      (node (ref "U10") (pin "1") (pinfunction "EN_1") (pintype "bidirectional"))
      (node (ref "U10") (pin "10") (pinfunction "GND_10") (pintype "bidirectional"))
      (node (ref "U11") (pin "5") (pinfunction "V+_5") (pintype "power_in"))
      (node (ref "U12") (pin "3") (pinfunction "GND_3") (pintype "bidirectional"))
      (node (ref "U13") (pin "3") (pinfunction "GND_3") (pintype "bidirectional"))
      (node (ref "U14") (pin "2") (pinfunction "GND_2") (pintype "bidirectional"))
      (node (ref "U15") (pin "2") (pinfunction "GND_2") (pintype "bidirectional"))
      (node (ref "U16") (pin "5") (pinfunction "V+_5") (pintype "power_in"))
      (node (ref "U17") (pin "5") (pinfunction "V+_5") (pintype "power_in"))
      (node (ref "U2") (pin "7") (pinfunction "GND_7") (pintype "bidirectional"))
      (node (ref "U3") (pin "8") (pinfunction "GND_8") (pintype "bidirectional"))
      (node (ref "U4") (pin "2") (pinfunction "GND_2") (pintype "bidirectional"))
      (node (ref "U5") (pin "3") (pinfunction "GND_3") (pintype "bidirectional"))
      (node (ref "U6") (pin "4") (pinfunction "GND_4") (pintype "bidirectional"))
      (node (ref "U7") (pin "5") (pinfunction "GND_5") (pintype "bidirectional"))
      (node (ref "U8") (pin "3") (pinfunction "GND_3") (pintype "bidirectional"))
      (node (ref "U9") (pin "3") (pinfunction "GND_3") (pintype "bidirectional"))
      (node (ref "X1") (pin "193") (pinfunction "1_193") (pintype "passive"))
      (node (ref "X1") (pin "194") (pinfunction "1_194") (pintype "passive"))
      (node (ref "X1") (pin "195") (pinfunction "1_195") (pintype "passive"))
      (node (ref "X1") (pin "196") (pinfunction "1_196") (pintype "passive"))
      (node (ref "X1") (pin "197") (pinfunction "1_197") (pintype "passive"))
      (node (ref "X1") (pin "198") (pinfunction "1_198") (pintype "passive"))
      (node (ref "X1") (pin "199") (pinfunction "1_199") (pintype "passive"))
      (node (ref "X1") (pin "200") (pinfunction "1_200") (pintype "passive"))
    )
    (net (code "15") (name "IMD") (class "Default")
      (node (ref "U10") (pin "3") (pinfunction "IN2_3") (pintype "bidirectional"))
      (node (ref "X1") (pin "179") (pinfunction "1_179") (pintype "passive"))
    )
    (net (code "16") (name "IMD-R-SET") (class "Default")
      (node (ref "JP2") (pin "1") (pinfunction "1_1") (pintype "passive"))
      (node (ref "U13") (pin "4") (pinfunction "Y_4") (pintype "bidirectional"))
      (node (ref "X1") (pin "51") (pinfunction "1_51") (pintype "passive"))
    )
    (net (code "17") (name "IMD-SIG") (class "Default")
      (node (ref "R9") (pin "2") (pinfunction "2_2") (pintype "passive"))
      (node (ref "X1") (pin "47") (pinfunction "1_47") (pintype "passive"))
    )
    (net (code "18") (name "IMD_O") (class "Default")
      (node (ref "U1") (pin "37") (pinfunction "RC3_37") (pintype "bidirectional"))
      (node (ref "U10") (pin "18") (pinfunction "OUT2_18") (pintype "bidirectional"))
    )
    (net (code "19") (name "IMD_STAT") (class "Default")
      (node (ref "JP2") (pin "2") (pinfunction "2_2") (pintype "passive"))
      (node (ref "R10") (pin "2") (pinfunction "2_2") (pintype "passive"))
      (node (ref "R27") (pin "2") (pinfunction "2_2") (pintype "passive"))
      (node (ref "R9") (pin "1") (pinfunction "1_1") (pintype "passive"))
      (node (ref "U1") (pin "31") (pinfunction "RA6_31") (pintype "bidirectional"))
      (node (ref "U13") (pin "2") (pinfunction "A_2") (pintype "bidirectional"))
    )
    (net (code "20") (name "IS_O") (class "Default")
      (node (ref "R17") (pin "1") (pinfunction "1_1") (pintype "passive"))
      (node (ref "R18") (pin "2") (pinfunction "2_2") (pintype "passive"))
      (node (ref "U1") (pin "30") (pinfunction "RA7_30") (pintype "bidirectional"))
    )
    (net (code "21") (name "MAIN") (class "Default")
      (node (ref "R48") (pin "2") (pinfunction "2_2") (pintype "passive"))
      (node (ref "R7") (pin "2") (pinfunction "2_2") (pintype "passive"))
      (node (ref "U8") (pin "4") (pinfunction "Y_4") (pintype "bidirectional"))
      (node (ref "X1") (pin "43") (pinfunction "1_43") (pintype "passive"))
    )
    (net (code "22") (name "Net-(LED1-PadA)") (class "Default")
      (node (ref "LED1") (pin "A") (pinfunction "A_A") (pintype "passive"))
      (node (ref "R20") (pin "1") (pinfunction "1_1") (pintype "passive"))
    )
    (net (code "23") (name "Net-(LED4-PadA)") (class "Default")
      (node (ref "LED4") (pin "A") (pinfunction "A_A") (pintype "passive"))
      (node (ref "R48") (pin "1") (pinfunction "1_1") (pintype "passive"))
    )
    (net (code "24") (name "Net-(LED5-PadA)") (class "Default")
      (node (ref "LED5") (pin "A") (pinfunction "A_A") (pintype "passive"))
      (node (ref "R49") (pin "1") (pinfunction "1_1") (pintype "passive"))
    )
    (net (code "25") (name "Net-(LED6-PadA)") (class "Default")
      (node (ref "LED6") (pin "A") (pinfunction "A_A") (pintype "passive"))
      (node (ref "R50") (pin "1") (pinfunction "1_1") (pintype "passive"))
    )
    (net (code "26") (name "Net-(LED7-PadA)") (class "Default")
      (node (ref "LED7") (pin "A") (pinfunction "A_A") (pintype "passive"))
      (node (ref "R1") (pin "1") (pinfunction "1_1") (pintype "passive"))
    )
    (net (code "27") (name "Net-(LED8-PadA)") (class "Default")
      (node (ref "LED8") (pin "A") (pinfunction "A_A") (pintype "passive"))
      (node (ref "R26") (pin "1") (pinfunction "1_1") (pintype "passive"))
    )
    (net (code "28") (name "Net-(LED9-PadA)") (class "Default")
      (node (ref "LED9") (pin "A") (pinfunction "A_A") (pintype "passive"))
      (node (ref "R27") (pin "1") (pinfunction "1_1") (pintype "passive"))
    )
    (net (code "29") (name "Net-(POT2-W)") (class "Default")
      (node (ref "C7") (pin "1") (pinfunction "1_1") (pintype "passive"))
      (node (ref "POT2") (pin "2") (pinfunction "W_2") (pintype "passive"))
      (node (ref "U17") (pin "4") (pinfunction "-IN_4") (pintype "input"))
    )
    (net (code "30") (name "Net-(POT3-W)") (class "Default")
      (node (ref "C3") (pin "1") (pinfunction "1_1") (pintype "passive"))
      (node (ref "CST") (pin "1") (pinfunction "P$1_1") (pintype "bidirectional"))
      (node (ref "CST") (pin "2") (pinfunction "P$1_2") (pintype "bidirectional"))
      (node (ref "POT3") (pin "2") (pinfunction "W_2") (pintype "passive"))
      (node (ref "U6") (pin "2") (pinfunction "INVI1_2") (pintype "bidirectional"))
    )
    (net (code "31") (name "Net-(POT4-W)") (class "Default")
      (node (ref "C8") (pin "1") (pinfunction "1_1") (pintype "passive"))
      (node (ref "PCG") (pin "1") (pinfunction "P$1_1") (pintype "bidirectional"))
      (node (ref "PCG") (pin "2") (pinfunction "P$1_2") (pintype "bidirectional"))
      (node (ref "POT4") (pin "2") (pinfunction "W_2") (pintype "passive"))
      (node (ref "U6") (pin "6") (pinfunction "INVI2_6") (pintype "bidirectional"))
    )
    (net (code "32") (name "Net-(POT5-W)") (class "Default")
      (node (ref "C25") (pin "1") (pinfunction "1_1") (pintype "passive"))
      (node (ref "POT5") (pin "2") (pinfunction "W_2") (pintype "passive"))
      (node (ref "RST") (pin "1") (pinfunction "P$1_1") (pintype "bidirectional"))
      (node (ref "RST") (pin "2") (pinfunction "P$1_2") (pintype "bidirectional"))
      (node (ref "U11") (pin "4") (pinfunction "-IN_4") (pintype "input"))
    )
    (net (code "33") (name "Net-(Q3-B)") (class "Default")
      (node (ref "Q3") (pin "1") (pinfunction "B_1") (pintype "passive"))
      (node (ref "R21") (pin "2") (pinfunction "2_2") (pintype "passive"))
    )
    (net (code "34") (name "Net-(Q3-E)") (class "Default")
      (node (ref "Q3") (pin "2") (pinfunction "E_2") (pintype "passive"))
      (node (ref "R5") (pin "1") (pinfunction "1_1") (pintype "passive"))
    )
    (net (code "35") (name "Net-(R39-Pad1)") (class "Default")
      (node (ref "R39") (pin "1") (pinfunction "1_1") (pintype "passive"))
      (node (ref "RX1") (pin "A") (pinfunction "A_A") (pintype "passive"))
    )
    (net (code "36") (name "Net-(R40-Pad1)") (class "Default")
      (node (ref "R40") (pin "1") (pinfunction "1_1") (pintype "passive"))
      (node (ref "TX1") (pin "A") (pinfunction "A_A") (pintype "passive"))
    )
    (net (code "37") (name "Net-(U1-PGC{slash}RB6)") (class "Default")
      (node (ref "JP1") (pin "5") (pinfunction "5_5") (pintype "passive"))
      (node (ref "U1") (pin "16") (pinfunction "PGC/RB6_16") (pintype "bidirectional"))
    )
    (net (code "38") (name "Net-(U1-PGD{slash}RB7)") (class "Default")
      (node (ref "JP1") (pin "4") (pinfunction "4_4") (pintype "passive"))
      (node (ref "U1") (pin "17") (pinfunction "PGD/RB7_17") (pintype "bidirectional"))
    )
    (net (code "39") (name "Net-(U1-RA3)") (class "Default")
      (node (ref "R20") (pin "2") (pinfunction "2_2") (pintype "passive"))
      (node (ref "U1") (pin "22") (pinfunction "RA3_22") (pintype "bidirectional"))
    )
    (net (code "40") (name "Net-(U1-~{MCLR})") (class "Default")
      (node (ref "JP1") (pin "1") (pinfunction "1_1") (pintype "passive"))
      (node (ref "R4") (pin "1") (pinfunction "1_1") (pintype "passive"))
      (node (ref "SJ1") (pin "2") (pinfunction "2_2") (pintype "passive"))
      (node (ref "U1") (pin "18") (pinfunction "~{MCLR}_18") (pintype "bidirectional"))
    )
    (net (code "41") (name "Net-(U2-1A)") (class "Default")
      (node (ref "U2") (pin "1") (pinfunction "1A_1") (pintype "bidirectional"))
      (node (ref "U3") (pin "5") (pinfunction "Q1A_5") (pintype "bidirectional"))
    )
    (net (code "42") (name "Net-(U2-1B)") (class "Default")
      (node (ref "U2") (pin "2") (pinfunction "1B_2") (pintype "bidirectional"))
      (node (ref "U3") (pin "4") (pinfunction "Q2A_4") (pintype "bidirectional"))
    )
    (net (code "43") (name "Net-(U2-1C)") (class "Default")
      (node (ref "U2") (pin "4") (pinfunction "1C_4") (pintype "bidirectional"))
      (node (ref "U3") (pin "3") (pinfunction "Q3A_3") (pintype "bidirectional"))
    )
    (net (code "44") (name "Net-(U2-1D)") (class "Default")
      (node (ref "U2") (pin "5") (pinfunction "1D_5") (pintype "bidirectional"))
      (node (ref "U3") (pin "10") (pinfunction "Q4A_10") (pintype "bidirectional"))
    )
    (net (code "45") (name "Net-(U3-CLKA)") (class "Default")
      (node (ref "CLK") (pin "1") (pinfunction "P$1_1") (pintype "bidirectional"))
      (node (ref "CLK") (pin "2") (pinfunction "P$1_2") (pintype "bidirectional"))
      (node (ref "U3") (pin "9") (pinfunction "CLKA_9") (pintype "bidirectional"))
      (node (ref "U4") (pin "6") (pinfunction "OUT_6") (pintype "bidirectional"))
    )
    (net (code "46") (name "Net-(U3-DAT-A)") (class "Default")
      (node (ref "U3") (pin "7") (pinfunction "DAT-A_7") (pintype "bidirectional"))
      (node (ref "U5") (pin "4") (pinfunction "Y_4") (pintype "bidirectional"))
    )
    (net (code "47") (name "Net-(U3-~{RSA})") (class "Default")
      (node (ref "JP11") (pin "1") (pinfunction "1_1") (pintype "passive"))
      (node (ref "R22") (pin "2") (pinfunction "2_2") (pintype "passive"))
      (node (ref "U3") (pin "6") (pinfunction "~{RSA}_6") (pintype "bidirectional"))
    )
    (net (code "48") (name "Net-(U4-DIV)") (class "Default")
      (node (ref "R30") (pin "1") (pinfunction "1_1") (pintype "passive"))
      (node (ref "R31") (pin "2") (pinfunction "2_2") (pintype "passive"))
      (node (ref "U4") (pin "4") (pinfunction "DIV_4") (pintype "bidirectional"))
    )
    (net (code "49") (name "Net-(U4-RST)") (class "Default")
      (node (ref "R32") (pin "1") (pinfunction "1_1") (pintype "passive"))
      (node (ref "R33") (pin "2") (pinfunction "2_2") (pintype "passive"))
      (node (ref "U4") (pin "1") (pinfunction "RST_1") (pintype "bidirectional"))
    )
    (net (code "50") (name "Net-(U4-SET)") (class "Default")
      (node (ref "R29") (pin "1") (pinfunction "1_1") (pintype "passive"))
      (node (ref "U4") (pin "3") (pinfunction "SET_3") (pintype "bidirectional"))
    )
    (net (code "51") (name "Net-(U5-A)") (class "Default")
      (node (ref "R14") (pin "1") (pinfunction "1_1") (pintype "passive"))
      (node (ref "U5") (pin "1") (pinfunction "A_1") (pintype "bidirectional"))
      (node (ref "U6") (pin "1") (pinfunction "O1_1") (pintype "bidirectional"))
    )
    (net (code "52") (name "Net-(U5-B)") (class "Default")
      (node (ref "R13") (pin "1") (pinfunction "1_1") (pintype "passive"))
      (node (ref "U5") (pin "2") (pinfunction "B_2") (pintype "bidirectional"))
      (node (ref "U6") (pin "7") (pinfunction "O2_7") (pintype "bidirectional"))
    )
    (net (code "53") (name "Net-(U11-+IN)") (class "Default")
      (node (ref "C24") (pin "1") (pinfunction "1_1") (pintype "passive"))
      (node (ref "R24") (pin "2") (pinfunction "2_2") (pintype "passive"))
      (node (ref "U$2") (pin "1") (pinfunction "P$1_1") (pintype "bidirectional"))
      (node (ref "U$2") (pin "2") (pinfunction "P$1_2") (pintype "bidirectional"))
      (node (ref "U11") (pin "3") (pinfunction "+IN_3") (pintype "input"))
    )
    (net (code "54") (name "Net-(U11-OUT)") (class "Default")
      (node (ref "R25") (pin "2") (pinfunction "2_2") (pintype "passive"))
      (node (ref "R36") (pin "1") (pinfunction "1_1") (pintype "passive"))
      (node (ref "U11") (pin "1") (pinfunction "OUT_1") (pintype "output"))
      (node (ref "U12") (pin "2") (pinfunction "B_2") (pintype "bidirectional"))
    )
    (net (code "55") (name "Net-(U15-~{RST})") (class "Default")
      (node (ref "SJ1") (pin "1") (pinfunction "1_1") (pintype "passive"))
      (node (ref "U15") (pin "1") (pinfunction "~{RST}_1") (pintype "bidirectional"))
    )
    (net (code "56") (name "Net-(U16--IN)") (class "Default")
      (node (ref "U16") (pin "4") (pinfunction "-IN_4") (pintype "input"))
      (node (ref "U9") (pin "2") (pinfunction "OUT_2") (pintype "bidirectional"))
    )
    (net (code "57") (name "Net-(U17-+IN)") (class "Default")
      (node (ref "C6") (pin "1") (pinfunction "1_1") (pintype "passive"))
      (node (ref "R2") (pin "2") (pinfunction "2_2") (pintype "passive"))
      (node (ref "R5") (pin "2") (pinfunction "2_2") (pintype "passive"))
      (node (ref "U17") (pin "3") (pinfunction "+IN_3") (pintype "input"))
    )
    (net (code "58") (name "Net-(U17-OUT)") (class "Default")
      (node (ref "R50") (pin "2") (pinfunction "2_2") (pintype "passive"))
      (node (ref "R6") (pin "1") (pinfunction "1_1") (pintype "passive"))
      (node (ref "U17") (pin "1") (pinfunction "OUT_1") (pintype "output"))
      (node (ref "U8") (pin "2") (pinfunction "B_2") (pintype "bidirectional"))
    )
    (net (code "59") (name "Net-(X1CG-1)") (class "Default")
      (node (ref "R17") (pin "2") (pinfunction "2_2") (pintype "passive"))
      (node (ref "X1") (pin "175") (pinfunction "1_175") (pintype "passive"))
    )
    (net (code "60") (name "RELAY-SET") (class "Default")
      (node (ref "R26") (pin "2") (pinfunction "2_2") (pintype "passive"))
      (node (ref "R37") (pin "2") (pinfunction "2_2") (pintype "passive"))
      (node (ref "U$3") (pin "1") (pinfunction "P$1_1") (pintype "bidirectional"))
      (node (ref "U$3") (pin "2") (pinfunction "P$1_2") (pintype "bidirectional"))
      (node (ref "U12") (pin "4") (pinfunction "Y_4") (pintype "bidirectional"))
      (node (ref "X1") (pin "53") (pinfunction "1_53") (pintype "passive"))
    )
    (net (code "61") (name "RS-A") (class "Default")
      (node (ref "R41") (pin "1") (pinfunction "1_1") (pintype "passive"))
      (node (ref "U7") (pin "6") (pinfunction "A_6") (pintype "bidirectional"))
      (node (ref "X1") (pin "85") (pinfunction "1_85") (pintype "passive"))
    )
    (net (code "62") (name "RS-B") (class "Default")
      (node (ref "R41") (pin "2") (pinfunction "2_2") (pintype "passive"))
      (node (ref "U7") (pin "7") (pinfunction "B_7") (pintype "bidirectional"))
      (node (ref "X1") (pin "87") (pinfunction "1_87") (pintype "passive"))
    )
    (net (code "63") (name "RTG") (class "Default")
      (node (ref "R1") (pin "2") (pinfunction "2_2") (pintype "passive"))
      (node (ref "R51") (pin "1") (pinfunction "1_1") (pintype "passive"))
      (node (ref "X1") (pin "39") (pinfunction "1_39") (pintype "passive"))
    )
    (net (code "64") (name "RTG_5V") (class "Default")
      (node (ref "R51") (pin "2") (pinfunction "2_2") (pintype "passive"))
      (node (ref "R52") (pin "1") (pinfunction "1_1") (pintype "passive"))
      (node (ref "U1") (pin "23") (pinfunction "RA4_23") (pintype "bidirectional"))
      (node (ref "U16") (pin "3") (pinfunction "+IN_3") (pintype "input"))
    )
    (net (code "65") (name "RX1") (class "Default")
      (node (ref "RX1") (pin "C") (pinfunction "C_C") (pintype "passive"))
      (node (ref "U1") (pin "1") (pinfunction "RC7_1") (pintype "bidirectional"))
      (node (ref "U7") (pin "1") (pinfunction "R_1") (pintype "bidirectional"))
    )
    (net (code "66") (name "SSW_C") (class "Default")
      (node (ref "U10") (pin "4") (pinfunction "IN3_4") (pintype "bidirectional"))
      (node (ref "X1") (pin "181") (pinfunction "1_181") (pintype "passive"))
    )
    (net (code "67") (name "SSW_C_O") (class "Default")
      (node (ref "U1") (pin "38") (pinfunction "RD0_38") (pintype "bidirectional"))
      (node (ref "U10") (pin "17") (pinfunction "OUT3_17") (pintype "bidirectional"))
    )
    (net (code "68") (name "SSW_L") (class "Default")
      (node (ref "U10") (pin "6") (pinfunction "IN5_6") (pintype "bidirectional"))
      (node (ref "X1") (pin "185") (pinfunction "1_185") (pintype "passive"))
    )
    (net (code "69") (name "SSW_L_O") (class "Default")
      (node (ref "U1") (pin "40") (pinfunction "RD2_40") (pintype "bidirectional"))
      (node (ref "U10") (pin "15") (pinfunction "OUT5_15") (pintype "bidirectional"))
    )
    (net (code "70") (name "SSW_R") (class "Default")
      (node (ref "U10") (pin "5") (pinfunction "IN4_5") (pintype "bidirectional"))
      (node (ref "X1") (pin "183") (pinfunction "1_183") (pintype "passive"))
    )
    (net (code "71") (name "SSW_R_O") (class "Default")
      (node (ref "U1") (pin "39") (pinfunction "RD1_39") (pintype "bidirectional"))
      (node (ref "U10") (pin "16") (pinfunction "OUT4_16") (pintype "bidirectional"))
    )
    (net (code "72") (name "START") (class "Default")
      (node (ref "R2") (pin "1") (pinfunction "1_1") (pintype "passive"))
      (node (ref "R21") (pin "1") (pinfunction "1_1") (pintype "passive"))
      (node (ref "R49") (pin "2") (pinfunction "2_2") (pintype "passive"))
      (node (ref "U16") (pin "1") (pinfunction "OUT_1") (pintype "output"))
      (node (ref "U8") (pin "1") (pinfunction "A_1") (pintype "bidirectional"))
      (node (ref "X1") (pin "41") (pinfunction "1_41") (pintype "passive"))
    )
    (net (code "73") (name "TSMS") (class "Default")
      (node (ref "U14") (pin "1") (pinfunction "IN1_1") (pintype "bidirectional"))
      (node (ref "X1") (pin "173") (pinfunction "1_173") (pintype "passive"))
    )
    (net (code "74") (name "TSMS_O") (class "Default")
      (node (ref "U1") (pin "35") (pinfunction "RC1_35") (pintype "bidirectional"))
      (node (ref "U14") (pin "6") (pinfunction "OUT1_6") (pintype "bidirectional"))
    )
    (net (code "75") (name "TX1") (class "Default")
      (node (ref "TX1") (pin "C") (pinfunction "C_C") (pintype "passive"))
      (node (ref "U1") (pin "44") (pinfunction "RC6_44") (pintype "bidirectional"))
      (node (ref "U7") (pin "4") (pinfunction "D_4") (pintype "bidirectional"))
    )
    (net (code "76") (name "U7-RE{slash}DE") (class "Default")
      (node (ref "U1") (pin "2") (pinfunction "RD4_2") (pintype "bidirectional"))
      (node (ref "U7") (pin "2") (pinfunction "~{RE}_2") (pintype "bidirectional"))
      (node (ref "U7") (pin "3") (pinfunction "DE_3") (pintype "bidirectional"))
    )
    (net (code "77") (name "WDT") (class "Default")
      (node (ref "U1") (pin "19") (pinfunction "RA0_19") (pintype "bidirectional"))
      (node (ref "U15") (pin "4") (pinfunction "WDI_4") (pintype "bidirectional"))
    )
    (net (code "78") (name "unconnected-(U1-RA1-Pad20)") (class "Default")
      (node (ref "U1") (pin "20") (pinfunction "RA1_20") (pintype "bidirectional"))
    )
    (net (code "79") (name "unconnected-(U1-RA2-Pad21)") (class "Default")
      (node (ref "U1") (pin "21") (pinfunction "RA2_21") (pintype "bidirectional"))
    )
    (net (code "80") (name "unconnected-(U1-RA5-Pad24)") (class "Default")
      (node (ref "U1") (pin "24") (pinfunction "RA5_24") (pintype "bidirectional"))
    )
    (net (code "81") (name "unconnected-(U1-RB0-Pad8)") (class "Default")
      (node (ref "U1") (pin "8") (pinfunction "RB0_8") (pintype "bidirectional"))
    )
    (net (code "82") (name "unconnected-(U1-RB1-Pad9)") (class "Default")
      (node (ref "U1") (pin "9") (pinfunction "RB1_9") (pintype "bidirectional"))
    )
    (net (code "83") (name "unconnected-(U1-RB2-Pad10)") (class "Default")
      (node (ref "U1") (pin "10") (pinfunction "RB2_10") (pintype "bidirectional"))
    )
    (net (code "84") (name "unconnected-(U1-RB3-Pad11)") (class "Default")
      (node (ref "U1") (pin "11") (pinfunction "RB3_11") (pintype "bidirectional"))
    )
    (net (code "85") (name "unconnected-(U1-RB4-Pad14)") (class "Default")
      (node (ref "U1") (pin "14") (pinfunction "RB4_14") (pintype "bidirectional"))
    )
    (net (code "86") (name "unconnected-(U1-RB5-Pad15)") (class "Default")
      (node (ref "U1") (pin "15") (pinfunction "RB5_15") (pintype "bidirectional"))
    )
    (net (code "87") (name "unconnected-(U1-RD5-Pad3)") (class "Default")
      (node (ref "U1") (pin "3") (pinfunction "RD5_3") (pintype "bidirectional"))
    )
    (net (code "88") (name "unconnected-(U1-RD6-Pad4)") (class "Default")
      (node (ref "U1") (pin "4") (pinfunction "RD6_4") (pintype "bidirectional"))
    )
    (net (code "89") (name "unconnected-(U1-RD7-Pad5)") (class "Default")
      (node (ref "U1") (pin "5") (pinfunction "RD7_5") (pintype "bidirectional"))
    )
    (net (code "90") (name "unconnected-(U1-RE0-Pad25)") (class "Default")
      (node (ref "U1") (pin "25") (pinfunction "RE0_25") (pintype "bidirectional"))
    )
    (net (code "91") (name "unconnected-(U1-RE1-Pad26)") (class "Default")
      (node (ref "U1") (pin "26") (pinfunction "RE1_26") (pintype "bidirectional"))
    )
    (net (code "92") (name "unconnected-(U1-RE2-Pad27)") (class "Default")
      (node (ref "U1") (pin "27") (pinfunction "RE2_27") (pintype "bidirectional"))
    )
    (net (code "93") (name "unconnected-(U2-2A-Pad9)") (class "Default")
      (node (ref "U2") (pin "9") (pinfunction "2A_9") (pintype "bidirectional"))
    )
    (net (code "94") (name "unconnected-(U2-2B-Pad10)") (class "Default")
      (node (ref "U2") (pin "10") (pinfunction "2B_10") (pintype "bidirectional"))
    )
    (net (code "95") (name "unconnected-(U2-2C-Pad12)") (class "Default")
      (node (ref "U2") (pin "12") (pinfunction "2C_12") (pintype "bidirectional"))
    )
    (net (code "96") (name "unconnected-(U2-2D-Pad13)") (class "Default")
      (node (ref "U2") (pin "13") (pinfunction "2D_13") (pintype "bidirectional"))
    )
    (net (code "97") (name "unconnected-(U2-2Y-Pad8)") (class "Default")
      (node (ref "U2") (pin "8") (pinfunction "2Y_8") (pintype "bidirectional"))
    )
    (net (code "98") (name "unconnected-(U3-CLKB-Pad1)") (class "Default")
      (node (ref "U3") (pin "1") (pinfunction "CLKB_1") (pintype "bidirectional"))
    )
    (net (code "99") (name "unconnected-(U3-DAT-B-Pad15)") (class "Default")
      (node (ref "U3") (pin "15") (pinfunction "DAT-B_15") (pintype "bidirectional"))
    )
    (net (code "100") (name "unconnected-(U3-Q1B-Pad13)") (class "Default")
      (node (ref "U3") (pin "13") (pinfunction "Q1B_13") (pintype "bidirectional"))
    )
    (net (code "101") (name "unconnected-(U3-Q2B-Pad12)") (class "Default")
      (node (ref "U3") (pin "12") (pinfunction "Q2B_12") (pintype "bidirectional"))
    )
    (net (code "102") (name "unconnected-(U3-Q3B-Pad11)") (class "Default")
      (node (ref "U3") (pin "11") (pinfunction "Q3B_11") (pintype "bidirectional"))
    )
    (net (code "103") (name "unconnected-(U3-Q4B-Pad2)") (class "Default")
      (node (ref "U3") (pin "2") (pinfunction "Q4B_2") (pintype "bidirectional"))
    )
    (net (code "104") (name "unconnected-(U3-~{RSTB}-Pad14)") (class "Default")
      (node (ref "U3") (pin "14") (pinfunction "~{RSTB}_14") (pintype "bidirectional"))
    )
    (net (code "105") (name "unconnected-(U10-CH-Pad11)") (class "Default")
      (node (ref "U10") (pin "11") (pinfunction "CH_11") (pintype "bidirectional"))
    )
    (net (code "106") (name "unconnected-(U14-IN2-Pad3)") (class "Default")
      (node (ref "U14") (pin "3") (pinfunction "IN2_3") (pintype "bidirectional"))
    )
    (net (code "107") (name "unconnected-(U15-~{MR}-Pad3)") (class "Default")
      (node (ref "U15") (pin "3") (pinfunction "~{MR}_3") (pintype "bidirectional"))
    )
    (net (code "108") (name "unconnected-(X1-Pad1)") (class "Default")
      (node (ref "X1") (pin "1") (pinfunction "1_1") (pintype "passive"))
    )
    (net (code "109") (name "unconnected-(X1AA-1-Pad122)") (class "Default")
      (node (ref "X1") (pin "122") (pinfunction "1_122") (pintype "passive"))
    )
    (net (code "110") (name "unconnected-(X1AB-1-Pad123)") (class "Default")
      (node (ref "X1") (pin "123") (pinfunction "1_123") (pintype "passive"))
    )
    (net (code "111") (name "unconnected-(X1AC-1-Pad124)") (class "Default")
      (node (ref "X1") (pin "124") (pinfunction "1_124") (pintype "passive"))
    )
    (net (code "112") (name "unconnected-(X1AD-1-Pad125)") (class "Default")
      (node (ref "X1") (pin "125") (pinfunction "1_125") (pintype "passive"))
    )
    (net (code "113") (name "unconnected-(X1AE-1-Pad126)") (class "Default")
      (node (ref "X1") (pin "126") (pinfunction "1_126") (pintype "passive"))
    )
    (net (code "114") (name "unconnected-(X1AF-1-Pad127)") (class "Default")
      (node (ref "X1") (pin "127") (pinfunction "1_127") (pintype "passive"))
    )
    (net (code "115") (name "unconnected-(X1AG-1-Pad128)") (class "Default")
      (node (ref "X1") (pin "128") (pinfunction "1_128") (pintype "passive"))
    )
    (net (code "116") (name "unconnected-(X1AH-1-Pad129)") (class "Default")
      (node (ref "X1") (pin "129") (pinfunction "1_129") (pintype "passive"))
    )
    (net (code "117") (name "unconnected-(X1AI-1-Pad13)") (class "Default")
      (node (ref "X1") (pin "13") (pinfunction "1_13") (pintype "passive"))
    )
    (net (code "118") (name "unconnected-(X1AJ-1-Pad130)") (class "Default")
      (node (ref "X1") (pin "130") (pinfunction "1_130") (pintype "passive"))
    )
    (net (code "119") (name "unconnected-(X1AK-1-Pad131)") (class "Default")
      (node (ref "X1") (pin "131") (pinfunction "1_131") (pintype "passive"))
    )
    (net (code "120") (name "unconnected-(X1AL-1-Pad132)") (class "Default")
      (node (ref "X1") (pin "132") (pinfunction "1_132") (pintype "passive"))
    )
    (net (code "121") (name "unconnected-(X1AM-1-Pad133)") (class "Default")
      (node (ref "X1") (pin "133") (pinfunction "1_133") (pintype "passive"))
    )
    (net (code "122") (name "unconnected-(X1AN-1-Pad134)") (class "Default")
      (node (ref "X1") (pin "134") (pinfunction "1_134") (pintype "passive"))
    )
    (net (code "123") (name "unconnected-(X1AO-1-Pad135)") (class "Default")
      (node (ref "X1") (pin "135") (pinfunction "1_135") (pintype "passive"))
    )
    (net (code "124") (name "unconnected-(X1AP-1-Pad136)") (class "Default")
      (node (ref "X1") (pin "136") (pinfunction "1_136") (pintype "passive"))
    )
    (net (code "125") (name "unconnected-(X1AQ-1-Pad137)") (class "Default")
      (node (ref "X1") (pin "137") (pinfunction "1_137") (pintype "passive"))
    )
    (net (code "126") (name "unconnected-(X1AR-1-Pad138)") (class "Default")
      (node (ref "X1") (pin "138") (pinfunction "1_138") (pintype "passive"))
    )
    (net (code "127") (name "unconnected-(X1AS-1-Pad139)") (class "Default")
      (node (ref "X1") (pin "139") (pinfunction "1_139") (pintype "passive"))
    )
    (net (code "128") (name "unconnected-(X1AT-1-Pad14)") (class "Default")
      (node (ref "X1") (pin "14") (pinfunction "1_14") (pintype "passive"))
    )
    (net (code "129") (name "unconnected-(X1AU-1-Pad140)") (class "Default")
      (node (ref "X1") (pin "140") (pinfunction "1_140") (pintype "passive"))
    )
    (net (code "130") (name "unconnected-(X1AV-1-Pad141)") (class "Default")
      (node (ref "X1") (pin "141") (pinfunction "1_141") (pintype "passive"))
    )
    (net (code "131") (name "unconnected-(X1AW-1-Pad142)") (class "Default")
      (node (ref "X1") (pin "142") (pinfunction "1_142") (pintype "passive"))
    )
    (net (code "132") (name "unconnected-(X1AX-1-Pad143)") (class "Default")
      (node (ref "X1") (pin "143") (pinfunction "1_143") (pintype "passive"))
    )
    (net (code "133") (name "unconnected-(X1AY-1-Pad144)") (class "Default")
      (node (ref "X1") (pin "144") (pinfunction "1_144") (pintype "passive"))
    )
    (net (code "134") (name "unconnected-(X1AZ-1-Pad145)") (class "Default")
      (node (ref "X1") (pin "145") (pinfunction "1_145") (pintype "passive"))
    )
    (net (code "135") (name "unconnected-(X1BA-1-Pad146)") (class "Default")
      (node (ref "X1") (pin "146") (pinfunction "1_146") (pintype "passive"))
    )
    (net (code "136") (name "unconnected-(X1BB-1-Pad147)") (class "Default")
      (node (ref "X1") (pin "147") (pinfunction "1_147") (pintype "passive"))
    )
    (net (code "137") (name "unconnected-(X1BC-1-Pad148)") (class "Default")
      (node (ref "X1") (pin "148") (pinfunction "1_148") (pintype "passive"))
    )
    (net (code "138") (name "unconnected-(X1BD-1-Pad149)") (class "Default")
      (node (ref "X1") (pin "149") (pinfunction "1_149") (pintype "passive"))
    )
    (net (code "139") (name "unconnected-(X1BE-1-Pad15)") (class "Default")
      (node (ref "X1") (pin "15") (pinfunction "1_15") (pintype "passive"))
    )
    (net (code "140") (name "unconnected-(X1BF-1-Pad150)") (class "Default")
      (node (ref "X1") (pin "150") (pinfunction "1_150") (pintype "passive"))
    )
    (net (code "141") (name "unconnected-(X1BG-1-Pad151)") (class "Default")
      (node (ref "X1") (pin "151") (pinfunction "1_151") (pintype "passive"))
    )
    (net (code "142") (name "unconnected-(X1BH-1-Pad152)") (class "Default")
      (node (ref "X1") (pin "152") (pinfunction "1_152") (pintype "passive"))
    )
    (net (code "143") (name "unconnected-(X1BI-1-Pad153)") (class "Default")
      (node (ref "X1") (pin "153") (pinfunction "1_153") (pintype "passive"))
    )
    (net (code "144") (name "unconnected-(X1BJ-1-Pad154)") (class "Default")
      (node (ref "X1") (pin "154") (pinfunction "1_154") (pintype "passive"))
    )
    (net (code "145") (name "unconnected-(X1BK-1-Pad155)") (class "Default")
      (node (ref "X1") (pin "155") (pinfunction "1_155") (pintype "passive"))
    )
    (net (code "146") (name "unconnected-(X1BL-1-Pad156)") (class "Default")
      (node (ref "X1") (pin "156") (pinfunction "1_156") (pintype "passive"))
    )
    (net (code "147") (name "unconnected-(X1BM-1-Pad157)") (class "Default")
      (node (ref "X1") (pin "157") (pinfunction "1_157") (pintype "passive"))
    )
    (net (code "148") (name "unconnected-(X1BN-1-Pad158)") (class "Default")
      (node (ref "X1") (pin "158") (pinfunction "1_158") (pintype "passive"))
    )
    (net (code "149") (name "unconnected-(X1BO-1-Pad159)") (class "Default")
      (node (ref "X1") (pin "159") (pinfunction "1_159") (pintype "passive"))
    )
    (net (code "150") (name "unconnected-(X1BP-1-Pad16)") (class "Default")
      (node (ref "X1") (pin "16") (pinfunction "1_16") (pintype "passive"))
    )
    (net (code "151") (name "unconnected-(X1BQ-1-Pad160)") (class "Default")
      (node (ref "X1") (pin "160") (pinfunction "1_160") (pintype "passive"))
    )
    (net (code "152") (name "unconnected-(X1BR-1-Pad161)") (class "Default")
      (node (ref "X1") (pin "161") (pinfunction "1_161") (pintype "passive"))
    )
    (net (code "153") (name "unconnected-(X1BS-1-Pad162)") (class "Default")
      (node (ref "X1") (pin "162") (pinfunction "1_162") (pintype "passive"))
    )
    (net (code "154") (name "unconnected-(X1BT-1-Pad163)") (class "Default")
      (node (ref "X1") (pin "163") (pinfunction "1_163") (pintype "passive"))
    )
    (net (code "155") (name "unconnected-(X1BU-1-Pad164)") (class "Default")
      (node (ref "X1") (pin "164") (pinfunction "1_164") (pintype "passive"))
    )
    (net (code "156") (name "unconnected-(X1BV-1-Pad165)") (class "Default")
      (node (ref "X1") (pin "165") (pinfunction "1_165") (pintype "passive"))
    )
    (net (code "157") (name "unconnected-(X1BW-1-Pad166)") (class "Default")
      (node (ref "X1") (pin "166") (pinfunction "1_166") (pintype "passive"))
    )
    (net (code "158") (name "unconnected-(X1BX-1-Pad167)") (class "Default")
      (node (ref "X1") (pin "167") (pinfunction "1_167") (pintype "passive"))
    )
    (net (code "159") (name "unconnected-(X1BY-1-Pad168)") (class "Default")
      (node (ref "X1") (pin "168") (pinfunction "1_168") (pintype "passive"))
    )
    (net (code "160") (name "unconnected-(X1BZ-1-Pad169)") (class "Default")
      (node (ref "X1") (pin "169") (pinfunction "1_169") (pintype "passive"))
    )
    (net (code "161") (name "unconnected-(X1C-1-Pad100)") (class "Default")
      (node (ref "X1") (pin "100") (pinfunction "1_100") (pintype "passive"))
    )
    (net (code "162") (name "unconnected-(X1CA-1-Pad17)") (class "Default")
      (node (ref "X1") (pin "17") (pinfunction "1_17") (pintype "passive"))
    )
    (net (code "163") (name "unconnected-(X1CB-1-Pad170)") (class "Default")
      (node (ref "X1") (pin "170") (pinfunction "1_170") (pintype "passive"))
    )
    (net (code "164") (name "unconnected-(X1CC-1-Pad171)") (class "Default")
      (node (ref "X1") (pin "171") (pinfunction "1_171") (pintype "passive"))
    )
    (net (code "165") (name "unconnected-(X1CD-1-Pad172)") (class "Default")
      (node (ref "X1") (pin "172") (pinfunction "1_172") (pintype "passive"))
    )
    (net (code "166") (name "unconnected-(X1CF-1-Pad174)") (class "Default")
      (node (ref "X1") (pin "174") (pinfunction "1_174") (pintype "passive"))
    )
    (net (code "167") (name "unconnected-(X1CH-1-Pad176)") (class "Default")
      (node (ref "X1") (pin "176") (pinfunction "1_176") (pintype "passive"))
    )
    (net (code "168") (name "unconnected-(X1CJ-1-Pad178)") (class "Default")
      (node (ref "X1") (pin "178") (pinfunction "1_178") (pintype "passive"))
    )
    (net (code "169") (name "unconnected-(X1CL-1-Pad18)") (class "Default")
      (node (ref "X1") (pin "18") (pinfunction "1_18") (pintype "passive"))
    )
    (net (code "170") (name "unconnected-(X1CM-1-Pad180)") (class "Default")
      (node (ref "X1") (pin "180") (pinfunction "1_180") (pintype "passive"))
    )
    (net (code "171") (name "unconnected-(X1CO-1-Pad182)") (class "Default")
      (node (ref "X1") (pin "182") (pinfunction "1_182") (pintype "passive"))
    )
    (net (code "172") (name "unconnected-(X1CQ-1-Pad184)") (class "Default")
      (node (ref "X1") (pin "184") (pinfunction "1_184") (pintype "passive"))
    )
    (net (code "173") (name "unconnected-(X1CS-1-Pad186)") (class "Default")
      (node (ref "X1") (pin "186") (pinfunction "1_186") (pintype "passive"))
    )
    (net (code "174") (name "unconnected-(X1CU-1-Pad188)") (class "Default")
      (node (ref "X1") (pin "188") (pinfunction "1_188") (pintype "passive"))
    )
    (net (code "175") (name "unconnected-(X1CW-1-Pad19)") (class "Default")
      (node (ref "X1") (pin "19") (pinfunction "1_19") (pintype "passive"))
    )
    (net (code "176") (name "unconnected-(X1CX-1-Pad190)") (class "Default")
      (node (ref "X1") (pin "190") (pinfunction "1_190") (pintype "passive"))
    )
    (net (code "177") (name "unconnected-(X1CZ-1-Pad192)") (class "Default")
      (node (ref "X1") (pin "192") (pinfunction "1_192") (pintype "passive"))
    )
    (net (code "178") (name "unconnected-(X1D-1-Pad101)") (class "Default")
      (node (ref "X1") (pin "101") (pinfunction "1_101") (pintype "passive"))
    )
    (net (code "179") (name "unconnected-(X1DH-1-Pad2)") (class "Default")
      (node (ref "X1") (pin "2") (pinfunction "1_2") (pintype "passive"))
    )
    (net (code "180") (name "unconnected-(X1DI-1-Pad20)") (class "Default")
      (node (ref "X1") (pin "20") (pinfunction "1_20") (pintype "passive"))
    )
    (net (code "181") (name "unconnected-(X1DK-1-Pad21)") (class "Default")
      (node (ref "X1") (pin "21") (pinfunction "1_21") (pintype "passive"))
    )
    (net (code "182") (name "unconnected-(X1DL-1-Pad22)") (class "Default")
      (node (ref "X1") (pin "22") (pinfunction "1_22") (pintype "passive"))
    )
    (net (code "183") (name "unconnected-(X1DM-1-Pad23)") (class "Default")
      (node (ref "X1") (pin "23") (pinfunction "1_23") (pintype "passive"))
    )
    (net (code "184") (name "unconnected-(X1DN-1-Pad24)") (class "Default")
      (node (ref "X1") (pin "24") (pinfunction "1_24") (pintype "passive"))
    )
    (net (code "185") (name "unconnected-(X1DO-1-Pad25)") (class "Default")
      (node (ref "X1") (pin "25") (pinfunction "1_25") (pintype "passive"))
    )
    (net (code "186") (name "unconnected-(X1DP-1-Pad26)") (class "Default")
      (node (ref "X1") (pin "26") (pinfunction "1_26") (pintype "passive"))
    )
    (net (code "187") (name "unconnected-(X1DQ-1-Pad27)") (class "Default")
      (node (ref "X1") (pin "27") (pinfunction "1_27") (pintype "passive"))
    )
    (net (code "188") (name "unconnected-(X1DR-1-Pad28)") (class "Default")
      (node (ref "X1") (pin "28") (pinfunction "1_28") (pintype "passive"))
    )
    (net (code "189") (name "unconnected-(X1DS-1-Pad29)") (class "Default")
      (node (ref "X1") (pin "29") (pinfunction "1_29") (pintype "passive"))
    )
    (net (code "190") (name "unconnected-(X1DT-1-Pad3)") (class "Default")
      (node (ref "X1") (pin "3") (pinfunction "1_3") (pintype "passive"))
    )
    (net (code "191") (name "unconnected-(X1DU-1-Pad30)") (class "Default")
      (node (ref "X1") (pin "30") (pinfunction "1_30") (pintype "passive"))
    )
    (net (code "192") (name "unconnected-(X1DV-1-Pad31)") (class "Default")
      (node (ref "X1") (pin "31") (pinfunction "1_31") (pintype "passive"))
    )
    (net (code "193") (name "unconnected-(X1DW-1-Pad32)") (class "Default")
      (node (ref "X1") (pin "32") (pinfunction "1_32") (pintype "passive"))
    )
    (net (code "194") (name "unconnected-(X1DX-1-Pad33)") (class "Default")
      (node (ref "X1") (pin "33") (pinfunction "1_33") (pintype "passive"))
    )
    (net (code "195") (name "unconnected-(X1DY-1-Pad34)") (class "Default")
      (node (ref "X1") (pin "34") (pinfunction "1_34") (pintype "passive"))
    )
    (net (code "196") (name "unconnected-(X1DZ-1-Pad35)") (class "Default")
      (node (ref "X1") (pin "35") (pinfunction "1_35") (pintype "passive"))
    )
    (net (code "197") (name "unconnected-(X1E-1-Pad102)") (class "Default")
      (node (ref "X1") (pin "102") (pinfunction "1_102") (pintype "passive"))
    )
    (net (code "198") (name "unconnected-(X1EA-1-Pad36)") (class "Default")
      (node (ref "X1") (pin "36") (pinfunction "1_36") (pintype "passive"))
    )
    (net (code "199") (name "unconnected-(X1EB-1-Pad37)") (class "Default")
      (node (ref "X1") (pin "37") (pinfunction "1_37") (pintype "passive"))
    )
    (net (code "200") (name "unconnected-(X1EC-1-Pad38)") (class "Default")
      (node (ref "X1") (pin "38") (pinfunction "1_38") (pintype "passive"))
    )
    (net (code "201") (name "unconnected-(X1EE-1-Pad4)") (class "Default")
      (node (ref "X1") (pin "4") (pinfunction "1_4") (pintype "passive"))
    )
    (net (code "202") (name "unconnected-(X1EF-1-Pad40)") (class "Default")
      (node (ref "X1") (pin "40") (pinfunction "1_40") (pintype "passive"))
    )
    (net (code "203") (name "unconnected-(X1EH-1-Pad42)") (class "Default")
      (node (ref "X1") (pin "42") (pinfunction "1_42") (pintype "passive"))
    )
    (net (code "204") (name "unconnected-(X1EJ-1-Pad44)") (class "Default")
      (node (ref "X1") (pin "44") (pinfunction "1_44") (pintype "passive"))
    )
    (net (code "205") (name "unconnected-(X1EK-1-Pad45)") (class "Default")
      (node (ref "X1") (pin "45") (pinfunction "1_45") (pintype "passive"))
    )
    (net (code "206") (name "unconnected-(X1EL-1-Pad46)") (class "Default")
      (node (ref "X1") (pin "46") (pinfunction "1_46") (pintype "passive"))
    )
    (net (code "207") (name "unconnected-(X1EN-1-Pad48)") (class "Default")
      (node (ref "X1") (pin "48") (pinfunction "1_48") (pintype "passive"))
    )
    (net (code "208") (name "unconnected-(X1EP-1-Pad5)") (class "Default")
      (node (ref "X1") (pin "5") (pinfunction "1_5") (pintype "passive"))
    )
    (net (code "209") (name "unconnected-(X1EQ-1-Pad50)") (class "Default")
      (node (ref "X1") (pin "50") (pinfunction "1_50") (pintype "passive"))
    )
    (net (code "210") (name "unconnected-(X1ES-1-Pad52)") (class "Default")
      (node (ref "X1") (pin "52") (pinfunction "1_52") (pintype "passive"))
    )
    (net (code "211") (name "unconnected-(X1EU-1-Pad54)") (class "Default")
      (node (ref "X1") (pin "54") (pinfunction "1_54") (pintype "passive"))
    )
    (net (code "212") (name "unconnected-(X1EV-1-Pad55)") (class "Default")
      (node (ref "X1") (pin "55") (pinfunction "1_55") (pintype "passive"))
    )
    (net (code "213") (name "unconnected-(X1EW-1-Pad56)") (class "Default")
      (node (ref "X1") (pin "56") (pinfunction "1_56") (pintype "passive"))
    )
    (net (code "214") (name "unconnected-(X1EX-1-Pad57)") (class "Default")
      (node (ref "X1") (pin "57") (pinfunction "1_57") (pintype "passive"))
    )
    (net (code "215") (name "unconnected-(X1EY-1-Pad58)") (class "Default")
      (node (ref "X1") (pin "58") (pinfunction "1_58") (pintype "passive"))
    )
    (net (code "216") (name "unconnected-(X1EZ-1-Pad59)") (class "Default")
      (node (ref "X1") (pin "59") (pinfunction "1_59") (pintype "passive"))
    )
    (net (code "217") (name "unconnected-(X1F-1-Pad103)") (class "Default")
      (node (ref "X1") (pin "103") (pinfunction "1_103") (pintype "passive"))
    )
    (net (code "218") (name "unconnected-(X1FA-1-Pad6)") (class "Default")
      (node (ref "X1") (pin "6") (pinfunction "1_6") (pintype "passive"))
    )
    (net (code "219") (name "unconnected-(X1FB-1-Pad60)") (class "Default")
      (node (ref "X1") (pin "60") (pinfunction "1_60") (pintype "passive"))
    )
    (net (code "220") (name "unconnected-(X1FC-1-Pad61)") (class "Default")
      (node (ref "X1") (pin "61") (pinfunction "1_61") (pintype "passive"))
    )
    (net (code "221") (name "unconnected-(X1FD-1-Pad62)") (class "Default")
      (node (ref "X1") (pin "62") (pinfunction "1_62") (pintype "passive"))
    )
    (net (code "222") (name "unconnected-(X1FE-1-Pad63)") (class "Default")
      (node (ref "X1") (pin "63") (pinfunction "1_63") (pintype "passive"))
    )
    (net (code "223") (name "unconnected-(X1FF-1-Pad64)") (class "Default")
      (node (ref "X1") (pin "64") (pinfunction "1_64") (pintype "passive"))
    )
    (net (code "224") (name "unconnected-(X1FG-1-Pad65)") (class "Default")
      (node (ref "X1") (pin "65") (pinfunction "1_65") (pintype "passive"))
    )
    (net (code "225") (name "unconnected-(X1FH-1-Pad66)") (class "Default")
      (node (ref "X1") (pin "66") (pinfunction "1_66") (pintype "passive"))
    )
    (net (code "226") (name "unconnected-(X1FJ-1-Pad68)") (class "Default")
      (node (ref "X1") (pin "68") (pinfunction "1_68") (pintype "passive"))
    )
    (net (code "227") (name "unconnected-(X1FM-1-Pad70)") (class "Default")
      (node (ref "X1") (pin "70") (pinfunction "1_70") (pintype "passive"))
    )
    (net (code "228") (name "unconnected-(X1FN-1-Pad71)") (class "Default")
      (node (ref "X1") (pin "71") (pinfunction "1_71") (pintype "passive"))
    )
    (net (code "229") (name "unconnected-(X1FO-1-Pad72)") (class "Default")
      (node (ref "X1") (pin "72") (pinfunction "1_72") (pintype "passive"))
    )
    (net (code "230") (name "unconnected-(X1FP-1-Pad73)") (class "Default")
      (node (ref "X1") (pin "73") (pinfunction "1_73") (pintype "passive"))
    )
    (net (code "231") (name "unconnected-(X1FQ-1-Pad74)") (class "Default")
      (node (ref "X1") (pin "74") (pinfunction "1_74") (pintype "passive"))
    )
    (net (code "232") (name "unconnected-(X1FS-1-Pad76)") (class "Default")
      (node (ref "X1") (pin "76") (pinfunction "1_76") (pintype "passive"))
    )
    (net (code "233") (name "unconnected-(X1FU-1-Pad78)") (class "Default")
      (node (ref "X1") (pin "78") (pinfunction "1_78") (pintype "passive"))
    )
    (net (code "234") (name "unconnected-(X1FX-1-Pad80)") (class "Default")
      (node (ref "X1") (pin "80") (pinfunction "1_80") (pintype "passive"))
    )
    (net (code "235") (name "unconnected-(X1FZ-1-Pad82)") (class "Default")
      (node (ref "X1") (pin "82") (pinfunction "1_82") (pintype "passive"))
    )
    (net (code "236") (name "unconnected-(X1G-1-Pad104)") (class "Default")
      (node (ref "X1") (pin "104") (pinfunction "1_104") (pintype "passive"))
    )
    (net (code "237") (name "unconnected-(X1GA-1-Pad83)") (class "Default")
      (node (ref "X1") (pin "83") (pinfunction "1_83") (pintype "passive"))
    )
    (net (code "238") (name "unconnected-(X1GB-1-Pad84)") (class "Default")
      (node (ref "X1") (pin "84") (pinfunction "1_84") (pintype "passive"))
    )
    (net (code "239") (name "unconnected-(X1GD-1-Pad86)") (class "Default")
      (node (ref "X1") (pin "86") (pinfunction "1_86") (pintype "passive"))
    )
    (net (code "240") (name "unconnected-(X1GF-1-Pad88)") (class "Default")
      (node (ref "X1") (pin "88") (pinfunction "1_88") (pintype "passive"))
    )
    (net (code "241") (name "unconnected-(X1GG-1-Pad89)") (class "Default")
      (node (ref "X1") (pin "89") (pinfunction "1_89") (pintype "passive"))
    )
    (net (code "242") (name "unconnected-(X1GI-1-Pad90)") (class "Default")
      (node (ref "X1") (pin "90") (pinfunction "1_90") (pintype "passive"))
    )
    (net (code "243") (name "unconnected-(X1GJ-1-Pad91)") (class "Default")
      (node (ref "X1") (pin "91") (pinfunction "1_91") (pintype "passive"))
    )
    (net (code "244") (name "unconnected-(X1GK-1-Pad92)") (class "Default")
      (node (ref "X1") (pin "92") (pinfunction "1_92") (pintype "passive"))
    )
    (net (code "245") (name "unconnected-(X1GL-1-Pad93)") (class "Default")
      (node (ref "X1") (pin "93") (pinfunction "1_93") (pintype "passive"))
    )
    (net (code "246") (name "unconnected-(X1GM-1-Pad94)") (class "Default")
      (node (ref "X1") (pin "94") (pinfunction "1_94") (pintype "passive"))
    )
    (net (code "247") (name "unconnected-(X1GN-1-Pad95)") (class "Default")
      (node (ref "X1") (pin "95") (pinfunction "1_95") (pintype "passive"))
    )
    (net (code "248") (name "unconnected-(X1GO-1-Pad96)") (class "Default")
      (node (ref "X1") (pin "96") (pinfunction "1_96") (pintype "passive"))
    )
    (net (code "249") (name "unconnected-(X1GP-1-Pad97)") (class "Default")
      (node (ref "X1") (pin "97") (pinfunction "1_97") (pintype "passive"))
    )
    (net (code "250") (name "unconnected-(X1GQ-1-Pad98)") (class "Default")
      (node (ref "X1") (pin "98") (pinfunction "1_98") (pintype "passive"))
    )
    (net (code "251") (name "unconnected-(X1GR-1-Pad99)") (class "Default")
      (node (ref "X1") (pin "99") (pinfunction "1_99") (pintype "passive"))
    )
    (net (code "252") (name "unconnected-(X1H-1-Pad105)") (class "Default")
      (node (ref "X1") (pin "105") (pinfunction "1_105") (pintype "passive"))
    )
    (net (code "253") (name "unconnected-(X1I-1-Pad106)") (class "Default")
      (node (ref "X1") (pin "106") (pinfunction "1_106") (pintype "passive"))
    )
    (net (code "254") (name "unconnected-(X1J-1-Pad107)") (class "Default")
      (node (ref "X1") (pin "107") (pinfunction "1_107") (pintype "passive"))
    )
    (net (code "255") (name "unconnected-(X1K-1-Pad108)") (class "Default")
      (node (ref "X1") (pin "108") (pinfunction "1_108") (pintype "passive"))
    )
    (net (code "256") (name "unconnected-(X1L-1-Pad109)") (class "Default")
      (node (ref "X1") (pin "109") (pinfunction "1_109") (pintype "passive"))
    )
    (net (code "257") (name "unconnected-(X1N-1-Pad110)") (class "Default")
      (node (ref "X1") (pin "110") (pinfunction "1_110") (pintype "passive"))
    )
    (net (code "258") (name "unconnected-(X1O-1-Pad111)") (class "Default")
      (node (ref "X1") (pin "111") (pinfunction "1_111") (pintype "passive"))
    )
    (net (code "259") (name "unconnected-(X1P-1-Pad112)") (class "Default")
      (node (ref "X1") (pin "112") (pinfunction "1_112") (pintype "passive"))
    )
    (net (code "260") (name "unconnected-(X1Q-1-Pad113)") (class "Default")
      (node (ref "X1") (pin "113") (pinfunction "1_113") (pintype "passive"))
    )
    (net (code "261") (name "unconnected-(X1R-1-Pad114)") (class "Default")
      (node (ref "X1") (pin "114") (pinfunction "1_114") (pintype "passive"))
    )
    (net (code "262") (name "unconnected-(X1S-1-Pad115)") (class "Default")
      (node (ref "X1") (pin "115") (pinfunction "1_115") (pintype "passive"))
    )
    (net (code "263") (name "unconnected-(X1T-1-Pad116)") (class "Default")
      (node (ref "X1") (pin "116") (pinfunction "1_116") (pintype "passive"))
    )
    (net (code "264") (name "unconnected-(X1U-1-Pad117)") (class "Default")
      (node (ref "X1") (pin "117") (pinfunction "1_117") (pintype "passive"))
    )
    (net (code "265") (name "unconnected-(X1V-1-Pad118)") (class "Default")
      (node (ref "X1") (pin "118") (pinfunction "1_118") (pintype "passive"))
    )
    (net (code "266") (name "unconnected-(X1W-1-Pad119)") (class "Default")
      (node (ref "X1") (pin "119") (pinfunction "1_119") (pintype "passive"))
    )
    (net (code "267") (name "unconnected-(X1Y-1-Pad120)") (class "Default")
      (node (ref "X1") (pin "120") (pinfunction "1_120") (pintype "passive"))
    )
    (net (code "268") (name "unconnected-(X1Z-1-Pad121)") (class "Default")
      (node (ref "X1") (pin "121") (pinfunction "1_121") (pintype "passive"))
    )
  )
)
